# PROTOTYPE_G431_4IN1_v1_0.net
KiCad netlist of a schematic drawn in Altium Designer
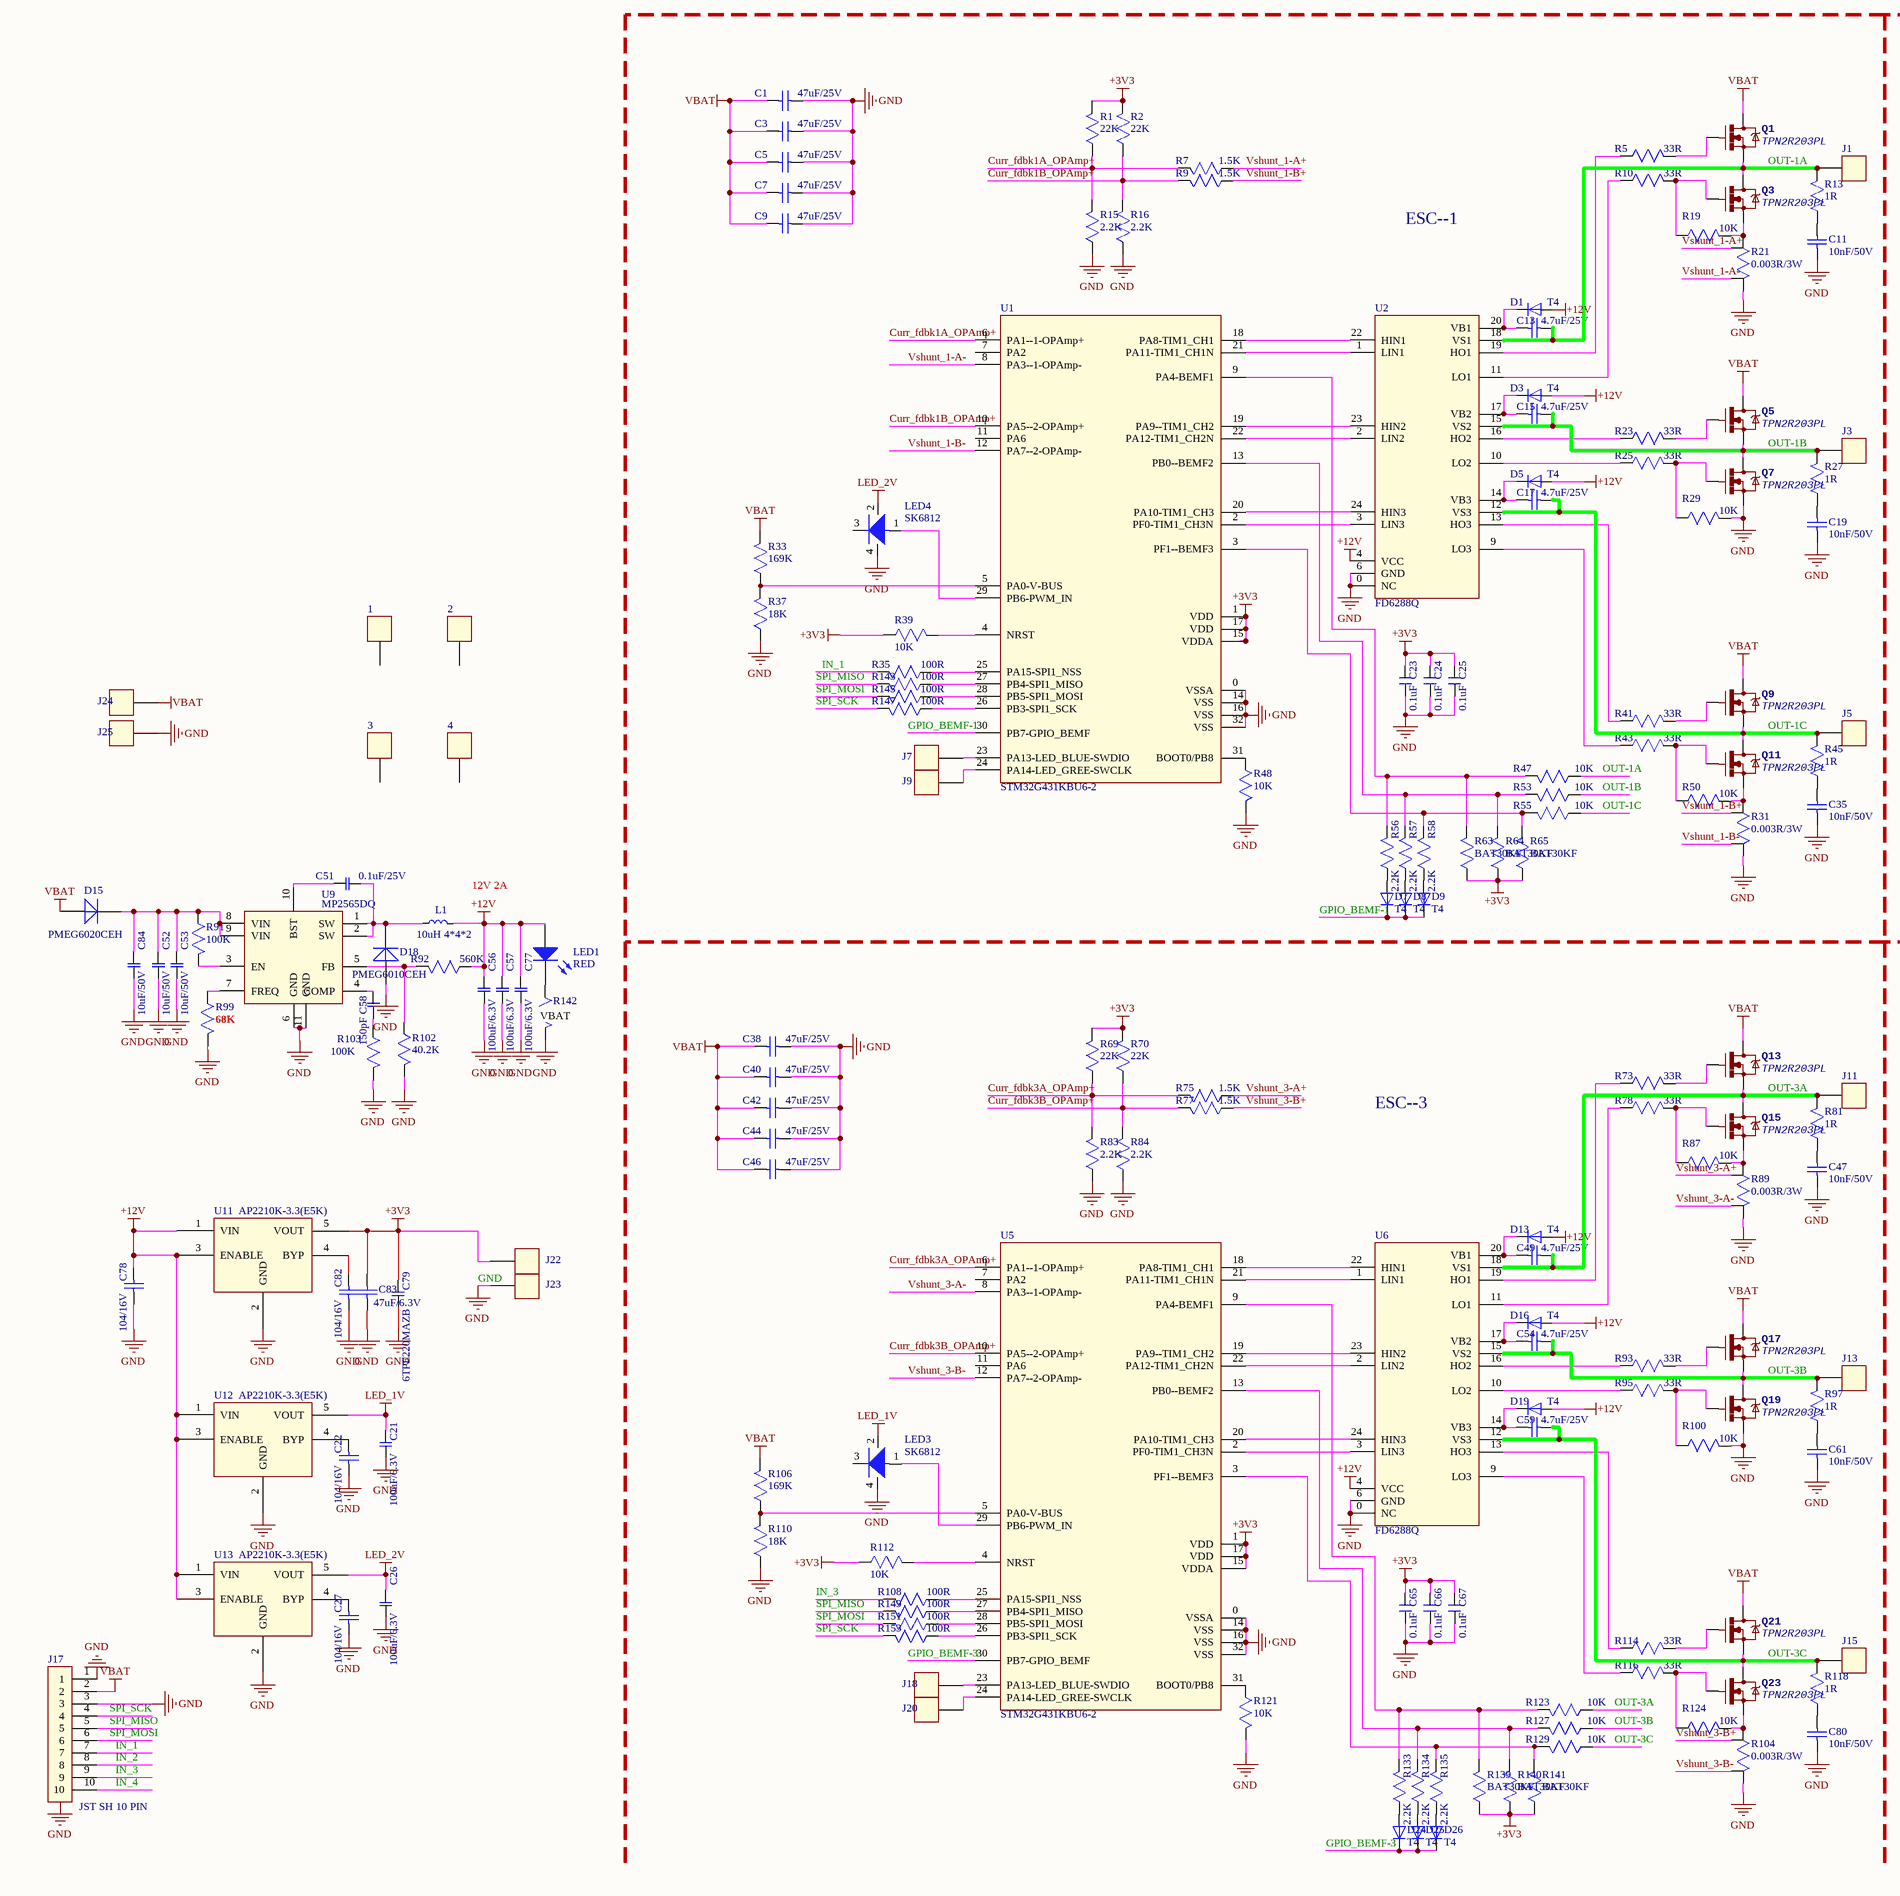
[diagram p0: PROTOTYPE_G431_4IN1_v1.0.SCHDOC, left]
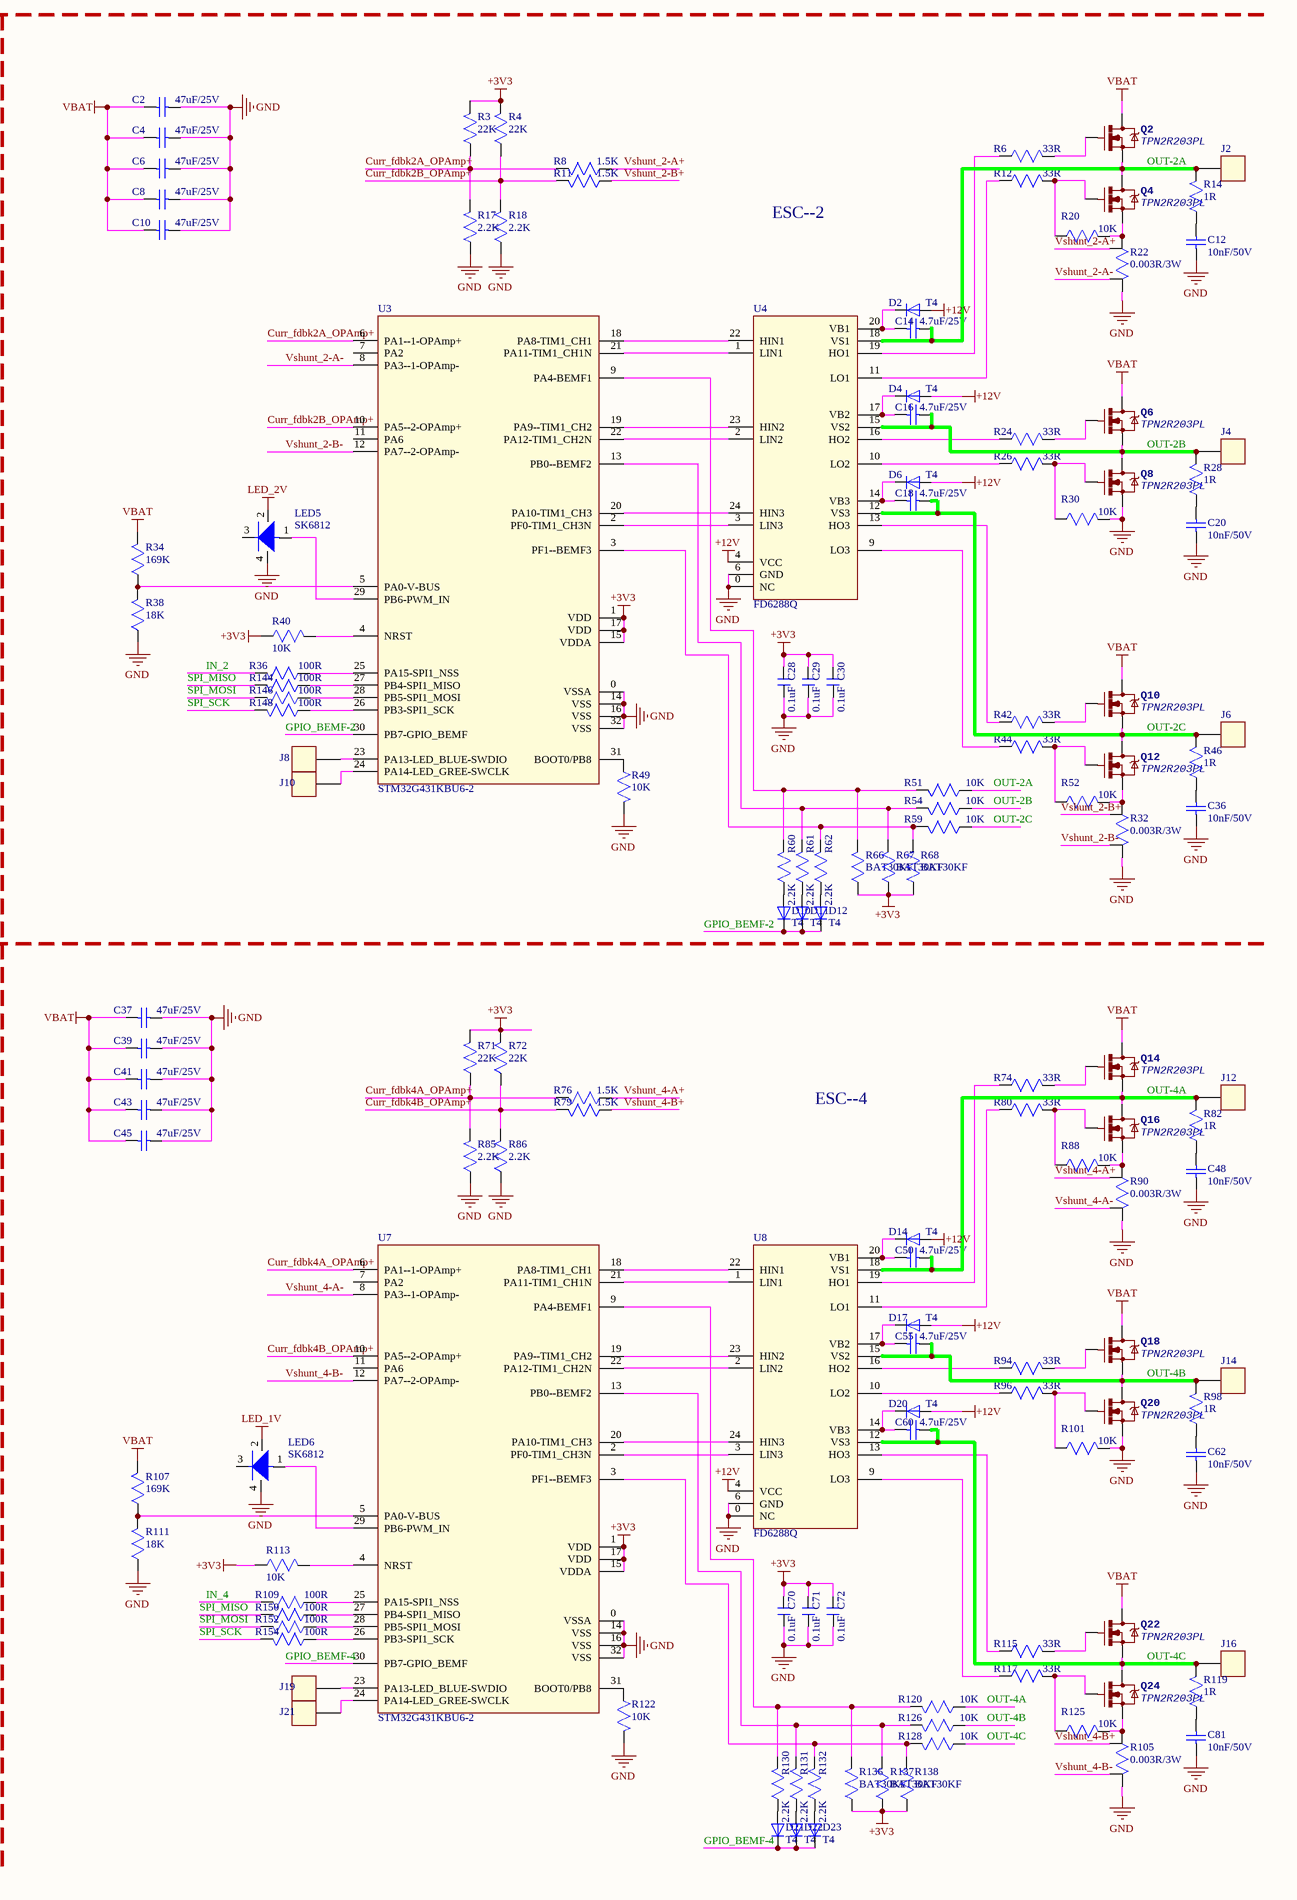
[diagram p1: PROTOTYPE_G431_4IN1_v1.0.SCHDOC, right]

(export (version "E")
  (design (tool "Eeschema 10.0.6"))
  (components
    (comp (ref "1") (value "~") (footprint "PAD-0.1") (libsource (lib "sf3") (part "PAD")))
    (comp (ref "2") (value "~") (footprint "PAD-0.1") (libsource (lib "sf3") (part "PAD")))
    (comp (ref "3") (value "~") (footprint "PAD-0.1") (libsource (lib "sf3") (part "PAD")))
    (comp (ref "4") (value "~") (footprint "PAD-0.1") (libsource (lib "sf3") (part "PAD")))
    (comp (ref "C1")
      (value "47uF/25V")
      (footprint "1206-RES")
      (description "Capacitor")
      (fields (field (name "PUBLISHER") "Altium Limited"))
      (libsource (lib "Miscellaneous Devices") (part "Cap"))
    )
    (comp (ref "C2")
      (value "47uF/25V")
      (footprint "1206-RES")
      (description "Capacitor")
      (fields (field (name "PUBLISHER") "Altium Limited"))
      (libsource (lib "Miscellaneous Devices") (part "Cap"))
    )
    (comp (ref "C3")
      (value "47uF/25V")
      (footprint "1206-RES")
      (description "Capacitor")
      (fields (field (name "PUBLISHER") "Altium Limited"))
      (libsource (lib "Miscellaneous Devices") (part "Cap"))
    )
    (comp (ref "C4")
      (value "47uF/25V")
      (footprint "1206-RES")
      (description "Capacitor")
      (fields (field (name "PUBLISHER") "Altium Limited"))
      (libsource (lib "Miscellaneous Devices") (part "Cap"))
    )
    (comp (ref "C5")
      (value "47uF/25V")
      (footprint "1206-RES")
      (description "Capacitor")
      (fields (field (name "PUBLISHER") "Altium Limited"))
      (libsource (lib "Miscellaneous Devices") (part "Cap"))
    )
    (comp (ref "C6")
      (value "47uF/25V")
      (footprint "1206-RES")
      (description "Capacitor")
      (fields (field (name "PUBLISHER") "Altium Limited"))
      (libsource (lib "Miscellaneous Devices") (part "Cap"))
    )
    (comp (ref "C7")
      (value "47uF/25V")
      (footprint "1206-RES")
      (description "Capacitor")
      (fields (field (name "PUBLISHER") "Altium Limited"))
      (libsource (lib "Miscellaneous Devices") (part "Cap"))
    )
    (comp (ref "C8")
      (value "47uF/25V")
      (footprint "1206-RES")
      (description "Capacitor")
      (fields (field (name "PUBLISHER") "Altium Limited"))
      (libsource (lib "Miscellaneous Devices") (part "Cap"))
    )
    (comp (ref "C9")
      (value "47uF/25V")
      (footprint "1206-RES")
      (description "Capacitor")
      (fields (field (name "PUBLISHER") "Altium Limited"))
      (libsource (lib "Miscellaneous Devices") (part "Cap"))
    )
    (comp (ref "C10")
      (value "47uF/25V")
      (footprint "1206-RES")
      (description "Capacitor")
      (fields (field (name "PUBLISHER") "Altium Limited"))
      (libsource (lib "Miscellaneous Devices") (part "Cap"))
    )
    (comp (ref "C11")
      (value "10nF/50V")
      (footprint "0402-RES")
      (fields (field (name "PUBLISHER") "Altium Limited"))
      (libsource (lib "DYS-XM30A V3.0") (part "Cap"))
    )
    (comp (ref "C12")
      (value "10nF/50V")
      (footprint "0402-RES")
      (fields (field (name "PUBLISHER") "Altium Limited"))
      (libsource (lib "DYS-XM30A V3.0") (part "Cap"))
    )
    (comp (ref "C13")
      (value "4.7uF/25V")
      (footprint "0603-RES")
      (fields (field (name "PUBLISHER") "Altium Limited"))
      (libsource (lib "DYS-XM30A V3.0") (part "Cap"))
    )
    (comp (ref "C14")
      (value "4.7uF/25V")
      (footprint "0603-RES")
      (fields (field (name "PUBLISHER") "Altium Limited"))
      (libsource (lib "DYS-XM30A V3.0") (part "Cap"))
    )
    (comp (ref "C15")
      (value "4.7uF/25V")
      (footprint "0603-RES")
      (fields (field (name "PUBLISHER") "Altium Limited"))
      (libsource (lib "DYS-XM30A V3.0") (part "Cap"))
    )
    (comp (ref "C16")
      (value "4.7uF/25V")
      (footprint "0603-RES")
      (fields (field (name "PUBLISHER") "Altium Limited"))
      (libsource (lib "DYS-XM30A V3.0") (part "Cap"))
    )
    (comp (ref "C17")
      (value "4.7uF/25V")
      (footprint "0603-RES")
      (fields (field (name "PUBLISHER") "Altium Limited"))
      (libsource (lib "DYS-XM30A V3.0") (part "Cap"))
    )
    (comp (ref "C18")
      (value "4.7uF/25V")
      (footprint "0603-RES")
      (fields (field (name "PUBLISHER") "Altium Limited"))
      (libsource (lib "DYS-XM30A V3.0") (part "Cap"))
    )
    (comp (ref "C19")
      (value "10nF/50V")
      (footprint "0402-RES")
      (fields (field (name "PUBLISHER") "Altium Limited"))
      (libsource (lib "DYS-XM30A V3.0") (part "Cap"))
    )
    (comp (ref "C20")
      (value "10nF/50V")
      (footprint "0402-RES")
      (fields (field (name "PUBLISHER") "Altium Limited"))
      (libsource (lib "DYS-XM30A V3.0") (part "Cap"))
    )
    (comp (ref "C21") (value "100uF/6.3V") (footprint "1206-RES") (libsource (lib "sf3") (part "C")))
    (comp (ref "C22")
      (value "104/16V")
      (footprint "0402-RES")
      (description "Capacitor")
      (fields (field (name "PUBLISHER") "Altium Limited"))
      (libsource (lib "Miscellaneous Devices") (part "Cap"))
    )
    (comp (ref "C23") (value "0.1uF") (footprint "0402-RES") (libsource (lib "USER-2016") (part "CAP")))
    (comp (ref "C24") (value "0.1uF") (footprint "0402-RES") (libsource (lib "USER-2016") (part "CAP")))
    (comp (ref "C25") (value "0.1uF") (footprint "0402-RES") (libsource (lib "USER-2016") (part "CAP")))
    (comp (ref "C26") (value "100uF/6.3V") (footprint "1206-RES") (libsource (lib "sf3") (part "C")))
    (comp (ref "C27")
      (value "104/16V")
      (footprint "0402-RES")
      (description "Capacitor")
      (fields (field (name "PUBLISHER") "Altium Limited"))
      (libsource (lib "Miscellaneous Devices") (part "Cap"))
    )
    (comp (ref "C28") (value "0.1uF") (footprint "0402-RES") (libsource (lib "USER-2016") (part "CAP")))
    (comp (ref "C29") (value "0.1uF") (footprint "0402-RES") (libsource (lib "USER-2016") (part "CAP")))
    (comp (ref "C30") (value "0.1uF") (footprint "0402-RES") (libsource (lib "USER-2016") (part "CAP")))
    (comp (ref "C35")
      (value "10nF/50V")
      (footprint "0402-RES")
      (fields (field (name "PUBLISHER") "Altium Limited"))
      (libsource (lib "DYS-XM30A V3.0") (part "Cap"))
    )
    (comp (ref "C36")
      (value "10nF/50V")
      (footprint "0402-RES")
      (fields (field (name "PUBLISHER") "Altium Limited"))
      (libsource (lib "DYS-XM30A V3.0") (part "Cap"))
    )
    (comp (ref "C37")
      (value "47uF/25V")
      (footprint "1206-RES")
      (description "Capacitor")
      (fields (field (name "PUBLISHER") "Altium Limited"))
      (libsource (lib "Miscellaneous Devices") (part "Cap"))
    )
    (comp (ref "C38")
      (value "47uF/25V")
      (footprint "1206-RES")
      (description "Capacitor")
      (fields (field (name "PUBLISHER") "Altium Limited"))
      (libsource (lib "Miscellaneous Devices") (part "Cap"))
    )
    (comp (ref "C39")
      (value "47uF/25V")
      (footprint "1206-RES")
      (description "Capacitor")
      (fields (field (name "PUBLISHER") "Altium Limited"))
      (libsource (lib "Miscellaneous Devices") (part "Cap"))
    )
    (comp (ref "C40")
      (value "47uF/25V")
      (footprint "1206-RES")
      (description "Capacitor")
      (fields (field (name "PUBLISHER") "Altium Limited"))
      (libsource (lib "Miscellaneous Devices") (part "Cap"))
    )
    (comp (ref "C41")
      (value "47uF/25V")
      (footprint "1206-RES")
      (description "Capacitor")
      (fields (field (name "PUBLISHER") "Altium Limited"))
      (libsource (lib "Miscellaneous Devices") (part "Cap"))
    )
    (comp (ref "C42")
      (value "47uF/25V")
      (footprint "1206-RES")
      (description "Capacitor")
      (fields (field (name "PUBLISHER") "Altium Limited"))
      (libsource (lib "Miscellaneous Devices") (part "Cap"))
    )
    (comp (ref "C43")
      (value "47uF/25V")
      (footprint "1206-RES")
      (description "Capacitor")
      (fields (field (name "PUBLISHER") "Altium Limited"))
      (libsource (lib "Miscellaneous Devices") (part "Cap"))
    )
    (comp (ref "C44")
      (value "47uF/25V")
      (footprint "1206-RES")
      (description "Capacitor")
      (fields (field (name "PUBLISHER") "Altium Limited"))
      (libsource (lib "Miscellaneous Devices") (part "Cap"))
    )
    (comp (ref "C45")
      (value "47uF/25V")
      (footprint "1206-RES")
      (description "Capacitor")
      (fields (field (name "PUBLISHER") "Altium Limited"))
      (libsource (lib "Miscellaneous Devices") (part "Cap"))
    )
    (comp (ref "C46")
      (value "47uF/25V")
      (footprint "1206-RES")
      (description "Capacitor")
      (fields (field (name "PUBLISHER") "Altium Limited"))
      (libsource (lib "Miscellaneous Devices") (part "Cap"))
    )
    (comp (ref "C47")
      (value "10nF/50V")
      (footprint "0402-RES")
      (fields (field (name "PUBLISHER") "Altium Limited"))
      (libsource (lib "DYS-XM30A V3.0") (part "Cap"))
    )
    (comp (ref "C48")
      (value "10nF/50V")
      (footprint "0402-RES")
      (fields (field (name "PUBLISHER") "Altium Limited"))
      (libsource (lib "DYS-XM30A V3.0") (part "Cap"))
    )
    (comp (ref "C49")
      (value "4.7uF/25V")
      (footprint "0603-RES")
      (fields (field (name "PUBLISHER") "Altium Limited"))
      (libsource (lib "DYS-XM30A V3.0") (part "Cap"))
    )
    (comp (ref "C50")
      (value "4.7uF/25V")
      (footprint "0603-RES")
      (fields (field (name "PUBLISHER") "Altium Limited"))
      (libsource (lib "DYS-XM30A V3.0") (part "Cap"))
    )
    (comp (ref "C51") (value "0.1uF/25V") (footprint "0402-RES") (libsource (lib "sf3") (part "C")))
    (comp (ref "C52") (value "10uF/50V") (footprint "1206-RES") (libsource (lib "sf3") (part "C")))
    (comp (ref "C53") (value "10uF/50V") (footprint "1206-RES") (libsource (lib "sf3") (part "C")))
    (comp (ref "C54")
      (value "4.7uF/25V")
      (footprint "0603-RES")
      (fields (field (name "PUBLISHER") "Altium Limited"))
      (libsource (lib "DYS-XM30A V3.0") (part "Cap"))
    )
    (comp (ref "C55")
      (value "4.7uF/25V")
      (footprint "0603-RES")
      (fields (field (name "PUBLISHER") "Altium Limited"))
      (libsource (lib "DYS-XM30A V3.0") (part "Cap"))
    )
    (comp (ref "C56") (value "100uF/6.3V") (footprint "1206-RES") (libsource (lib "sf3") (part "C")))
    (comp (ref "C57") (value "100uF/6.3V") (footprint "1206-RES") (libsource (lib "sf3") (part "C")))
    (comp (ref "C58") (value "150pF") (footprint "0402-RES") (libsource (lib "sf3") (part "C")))
    (comp (ref "C59")
      (value "4.7uF/25V")
      (footprint "0603-RES")
      (fields (field (name "PUBLISHER") "Altium Limited"))
      (libsource (lib "DYS-XM30A V3.0") (part "Cap"))
    )
    (comp (ref "C60")
      (value "4.7uF/25V")
      (footprint "0603-RES")
      (fields (field (name "PUBLISHER") "Altium Limited"))
      (libsource (lib "DYS-XM30A V3.0") (part "Cap"))
    )
    (comp (ref "C61")
      (value "10nF/50V")
      (footprint "0402-RES")
      (fields (field (name "PUBLISHER") "Altium Limited"))
      (libsource (lib "DYS-XM30A V3.0") (part "Cap"))
    )
    (comp (ref "C62")
      (value "10nF/50V")
      (footprint "0402-RES")
      (fields (field (name "PUBLISHER") "Altium Limited"))
      (libsource (lib "DYS-XM30A V3.0") (part "Cap"))
    )
    (comp (ref "C65") (value "0.1uF") (footprint "0402-RES") (libsource (lib "USER-2016") (part "CAP")))
    (comp (ref "C66") (value "0.1uF") (footprint "0402-RES") (libsource (lib "USER-2016") (part "CAP")))
    (comp (ref "C67") (value "0.1uF") (footprint "0402-RES") (libsource (lib "USER-2016") (part "CAP")))
    (comp (ref "C70") (value "0.1uF") (footprint "0402-RES") (libsource (lib "USER-2016") (part "CAP")))
    (comp (ref "C71") (value "0.1uF") (footprint "0402-RES") (libsource (lib "USER-2016") (part "CAP")))
    (comp (ref "C72") (value "0.1uF") (footprint "0402-RES") (libsource (lib "USER-2016") (part "CAP")))
    (comp (ref "C77") (value "100uF/6.3V") (footprint "1206-RES") (libsource (lib "sf3") (part "C")))
    (comp (ref "C78")
      (value "104/16V")
      (footprint "0402-RES")
      (description "Capacitor")
      (fields (field (name "PUBLISHER") "Altium Limited"))
      (libsource (lib "Miscellaneous Devices") (part "Cap"))
    )
    (comp (ref "C79") (value "6TPE220MAZB") (footprint "3528-CAP") (libsource (lib "USER-2016") (part "C")))
    (comp (ref "C80")
      (value "10nF/50V")
      (footprint "0402-RES")
      (fields (field (name "PUBLISHER") "Altium Limited"))
      (libsource (lib "DYS-XM30A V3.0") (part "Cap"))
    )
    (comp (ref "C81")
      (value "10nF/50V")
      (footprint "0402-RES")
      (fields (field (name "PUBLISHER") "Altium Limited"))
      (libsource (lib "DYS-XM30A V3.0") (part "Cap"))
    )
    (comp (ref "C82")
      (value "104/16V")
      (footprint "0402-RES")
      (description "Capacitor")
      (fields (field (name "PUBLISHER") "Altium Limited"))
      (libsource (lib "Miscellaneous Devices") (part "Cap"))
    )
    (comp (ref "C83")
      (value "47uF/6.3V")
      (footprint "0805-RES")
      (description "Capacitor")
      (fields (field (name "PUBLISHER") "Altium Limited"))
      (libsource (lib "Miscellaneous Devices") (part "Cap"))
    )
    (comp (ref "C84") (value "10uF/50V") (footprint "1206-RES") (libsource (lib "sf3") (part "C")))
    (comp (ref "D1") (value "T4") (footprint "SOD523") (libsource (lib "USER-2016") (part "DIODE")))
    (comp (ref "D2") (value "T4") (footprint "SOD523") (libsource (lib "USER-2016") (part "DIODE")))
    (comp (ref "D3") (value "T4") (footprint "SOD523") (libsource (lib "USER-2016") (part "DIODE")))
    (comp (ref "D4") (value "T4") (footprint "SOD523") (libsource (lib "USER-2016") (part "DIODE")))
    (comp (ref "D5") (value "T4") (footprint "SOD523") (libsource (lib "USER-2016") (part "DIODE")))
    (comp (ref "D6") (value "T4") (footprint "SOD523") (libsource (lib "USER-2016") (part "DIODE")))
    (comp (ref "D7") (value "T4") (footprint "SOD-723") (libsource (lib "USER-2016") (part "DIODE")))
    (comp (ref "D8") (value "T4") (footprint "SOD-723") (libsource (lib "USER-2016") (part "DIODE")))
    (comp (ref "D9") (value "T4") (footprint "SOD-723") (libsource (lib "USER-2016") (part "DIODE")))
    (comp (ref "D10") (value "T4") (footprint "SOD-723") (libsource (lib "USER-2016") (part "DIODE")))
    (comp (ref "D11") (value "T4") (footprint "SOD-723") (libsource (lib "USER-2016") (part "DIODE")))
    (comp (ref "D12") (value "T4") (footprint "SOD-723") (libsource (lib "USER-2016") (part "DIODE")))
    (comp (ref "D13") (value "T4") (footprint "SOD523") (libsource (lib "USER-2016") (part "DIODE")))
    (comp (ref "D14") (value "T4") (footprint "SOD523") (libsource (lib "USER-2016") (part "DIODE")))
    (comp (ref "D15") (value "PMEG6020CEH") (footprint "SOD123W") (libsource (lib "") (part "DIODE_1")))
    (comp (ref "D16") (value "T4") (footprint "SOD523") (libsource (lib "USER-2016") (part "DIODE")))
    (comp (ref "D17") (value "T4") (footprint "SOD523") (libsource (lib "USER-2016") (part "DIODE")))
    (comp (ref "D18") (value "PMEG6010CEH") (footprint "SOD123W") (libsource (lib "") (part "DIODE_1")))
    (comp (ref "D19") (value "T4") (footprint "SOD523") (libsource (lib "USER-2016") (part "DIODE")))
    (comp (ref "D20") (value "T4") (footprint "SOD523") (libsource (lib "USER-2016") (part "DIODE")))
    (comp (ref "D21") (value "T4") (footprint "SOD-723") (libsource (lib "USER-2016") (part "DIODE")))
    (comp (ref "D22") (value "T4") (footprint "SOD-723") (libsource (lib "USER-2016") (part "DIODE")))
    (comp (ref "D23") (value "T4") (footprint "SOD-723") (libsource (lib "USER-2016") (part "DIODE")))
    (comp (ref "D24") (value "T4") (footprint "SOD-723") (libsource (lib "USER-2016") (part "DIODE")))
    (comp (ref "D25") (value "T4") (footprint "SOD-723") (libsource (lib "USER-2016") (part "DIODE")))
    (comp (ref "D26") (value "T4") (footprint "SOD-723") (libsource (lib "USER-2016") (part "DIODE")))
    (comp (ref "J1") (value "~") (footprint "PAD-1  4*3") (libsource (lib "USER-2016") (part "PAD")))
    (comp (ref "J2") (value "~") (footprint "PAD-1  4*3") (libsource (lib "USER-2016") (part "PAD")))
    (comp (ref "J3") (value "~") (footprint "PAD-1  4*3") (libsource (lib "USER-2016") (part "PAD")))
    (comp (ref "J4") (value "~") (footprint "PAD-1  4*3") (libsource (lib "USER-2016") (part "PAD")))
    (comp (ref "J5") (value "~") (footprint "PAD-1  4*3") (libsource (lib "USER-2016") (part "PAD")))
    (comp (ref "J6") (value "~") (footprint "PAD-1  4*3") (libsource (lib "USER-2016") (part "PAD")))
    (comp (ref "J7") (value "~") (footprint "PAD-1  1*1.5") (libsource (lib "") (part "PAD_1")))
    (comp (ref "J8") (value "~") (footprint "PAD-1  1*1.5") (libsource (lib "") (part "PAD_1")))
    (comp (ref "J9") (value "~") (footprint "PAD-1  1*1.5") (libsource (lib "") (part "PAD_1")))
    (comp (ref "J10") (value "~") (footprint "PAD-1  1*1.5") (libsource (lib "") (part "PAD_1")))
    (comp (ref "J11") (value "~") (footprint "PAD-1  4*3") (libsource (lib "USER-2016") (part "PAD")))
    (comp (ref "J12") (value "~") (footprint "PAD-1  4*3") (libsource (lib "USER-2016") (part "PAD")))
    (comp (ref "J13") (value "~") (footprint "PAD-1  4*3") (libsource (lib "USER-2016") (part "PAD")))
    (comp (ref "J14") (value "~") (footprint "PAD-1  4*3") (libsource (lib "USER-2016") (part "PAD")))
    (comp (ref "J15") (value "~") (footprint "PAD-1  4*3") (libsource (lib "USER-2016") (part "PAD")))
    (comp (ref "J16") (value "~") (footprint "PAD-1  4*3") (libsource (lib "USER-2016") (part "PAD")))
    (comp (ref "J17")
      (value "JST SH 10 PIN")
      (footprint "JST SH 10 PIN")
      (libsource (lib "USER-2016") (part "J_10P"))
    )
    (comp (ref "J18") (value "~") (footprint "PAD-1  1*1.5") (libsource (lib "") (part "PAD_1")))
    (comp (ref "J19") (value "~") (footprint "PAD-1  1*1.5") (libsource (lib "") (part "PAD_1")))
    (comp (ref "J20") (value "~") (footprint "PAD-1  1*1.5") (libsource (lib "") (part "PAD_1")))
    (comp (ref "J21") (value "~") (footprint "PAD-1  1*1.5") (libsource (lib "") (part "PAD_1")))
    (comp (ref "J22") (value "~") (footprint "PAD-1  1*1.5") (libsource (lib "USER-2016") (part "PAD")))
    (comp (ref "J23") (value "~") (footprint "PAD-1  1*1.5") (libsource (lib "USER-2016") (part "PAD")))
    (comp (ref "J24") (value "~") (footprint "PAD-1  1*1.5") (libsource (lib "") (part "PAD_1")))
    (comp (ref "J25") (value "~") (footprint "PAD-1  1*1.5") (libsource (lib "") (part "PAD_1")))
    (comp (ref "L1") (value "10uH 4*4*2") (footprint "LPS4018") (libsource (lib "sf3") (part "L")))
    (comp (ref "LED1")
      (value "RED")
      (footprint "0402-LED")
      (fields (field (name "PUBLISHER") "Altium Limited"))
      (libsource (lib "sf3") (part "LED1"))
    )
    (comp (ref "LED3") (value "SK6812") (footprint "SK6812") (libsource (lib "USER-2016") (part "SK6812")))
    (comp (ref "LED4") (value "SK6812") (footprint "SK6812") (libsource (lib "USER-2016") (part "SK6812")))
    (comp (ref "LED5") (value "SK6812") (footprint "SK6812") (libsource (lib "USER-2016") (part "SK6812")))
    (comp (ref "LED6") (value "SK6812") (footprint "SK6812") (libsource (lib "USER-2016") (part "SK6812")))
    (comp (ref "Q1") (value "TPN2R203PL") (footprint "DFN8") (libsource (lib "Schlib1") (part "TPN2R304PL")))
    (comp (ref "Q2") (value "TPN2R203PL") (footprint "DFN8") (libsource (lib "Schlib1") (part "TPN2R304PL")))
    (comp (ref "Q3") (value "TPN2R203PL") (footprint "DFN8") (libsource (lib "Schlib1") (part "TPN2R304PL")))
    (comp (ref "Q4") (value "TPN2R203PL") (footprint "DFN8") (libsource (lib "Schlib1") (part "TPN2R304PL")))
    (comp (ref "Q5") (value "TPN2R203PL") (footprint "DFN8") (libsource (lib "Schlib1") (part "TPN2R304PL")))
    (comp (ref "Q6") (value "TPN2R203PL") (footprint "DFN8") (libsource (lib "Schlib1") (part "TPN2R304PL")))
    (comp (ref "Q7") (value "TPN2R203PL") (footprint "DFN8") (libsource (lib "Schlib1") (part "TPN2R304PL")))
    (comp (ref "Q8") (value "TPN2R203PL") (footprint "DFN8") (libsource (lib "Schlib1") (part "TPN2R304PL")))
    (comp (ref "Q9") (value "TPN2R203PL") (footprint "DFN8") (libsource (lib "Schlib1") (part "TPN2R304PL")))
    (comp (ref "Q10") (value "TPN2R203PL") (footprint "DFN8") (libsource (lib "Schlib1") (part "TPN2R304PL")))
    (comp (ref "Q11") (value "TPN2R203PL") (footprint "DFN8") (libsource (lib "Schlib1") (part "TPN2R304PL")))
    (comp (ref "Q12") (value "TPN2R203PL") (footprint "DFN8") (libsource (lib "Schlib1") (part "TPN2R304PL")))
    (comp (ref "Q13") (value "TPN2R203PL") (footprint "DFN8") (libsource (lib "Schlib1") (part "TPN2R304PL")))
    (comp (ref "Q14") (value "TPN2R203PL") (footprint "DFN8") (libsource (lib "Schlib1") (part "TPN2R304PL")))
    (comp (ref "Q15") (value "TPN2R203PL") (footprint "DFN8") (libsource (lib "Schlib1") (part "TPN2R304PL")))
    (comp (ref "Q16") (value "TPN2R203PL") (footprint "DFN8") (libsource (lib "Schlib1") (part "TPN2R304PL")))
    (comp (ref "Q17") (value "TPN2R203PL") (footprint "DFN8") (libsource (lib "Schlib1") (part "TPN2R304PL")))
    (comp (ref "Q18") (value "TPN2R203PL") (footprint "DFN8") (libsource (lib "Schlib1") (part "TPN2R304PL")))
    (comp (ref "Q19") (value "TPN2R203PL") (footprint "DFN8") (libsource (lib "Schlib1") (part "TPN2R304PL")))
    (comp (ref "Q20") (value "TPN2R203PL") (footprint "DFN8") (libsource (lib "Schlib1") (part "TPN2R304PL")))
    (comp (ref "Q21") (value "TPN2R203PL") (footprint "DFN8") (libsource (lib "Schlib1") (part "TPN2R304PL")))
    (comp (ref "Q22") (value "TPN2R203PL") (footprint "DFN8") (libsource (lib "Schlib1") (part "TPN2R304PL")))
    (comp (ref "Q23") (value "TPN2R203PL") (footprint "DFN8") (libsource (lib "Schlib1") (part "TPN2R304PL")))
    (comp (ref "Q24") (value "TPN2R203PL") (footprint "DFN8") (libsource (lib "Schlib1") (part "TPN2R304PL")))
    (comp (ref "R1") (value "22K") (footprint "0402-RES") (libsource (lib "sf3") (part "R")))
    (comp (ref "R2") (value "22K") (footprint "0402-RES") (libsource (lib "sf3") (part "R")))
    (comp (ref "R3") (value "22K") (footprint "0402-RES") (libsource (lib "sf3") (part "R")))
    (comp (ref "R4") (value "22K") (footprint "0402-RES") (libsource (lib "sf3") (part "R")))
    (comp (ref "R5") (value "33R") (footprint "0402-RES") (libsource (lib "USER-2016") (part "R")))
    (comp (ref "R6") (value "33R") (footprint "0402-RES") (libsource (lib "USER-2016") (part "R")))
    (comp (ref "R7") (value "1.5K") (footprint "0402-RES") (libsource (lib "sf3") (part "R")))
    (comp (ref "R8") (value "1.5K") (footprint "0402-RES") (libsource (lib "sf3") (part "R")))
    (comp (ref "R9") (value "1.5K") (footprint "0402-RES") (libsource (lib "sf3") (part "R")))
    (comp (ref "R10") (value "33R") (footprint "0402-RES") (libsource (lib "USER-2016") (part "R")))
    (comp (ref "R11") (value "1.5K") (footprint "0402-RES") (libsource (lib "sf3") (part "R")))
    (comp (ref "R12") (value "33R") (footprint "0402-RES") (libsource (lib "USER-2016") (part "R")))
    (comp (ref "R13") (value "1R") (footprint "0402-RES") (libsource (lib "USER-2016") (part "R")))
    (comp (ref "R14") (value "1R") (footprint "0402-RES") (libsource (lib "USER-2016") (part "R")))
    (comp (ref "R15") (value "2.2K") (footprint "0402-RES") (libsource (lib "sf3") (part "R")))
    (comp (ref "R16") (value "2.2K") (footprint "0402-RES") (libsource (lib "sf3") (part "R")))
    (comp (ref "R17") (value "2.2K") (footprint "0402-RES") (libsource (lib "sf3") (part "R")))
    (comp (ref "R18") (value "2.2K") (footprint "0402-RES") (libsource (lib "sf3") (part "R")))
    (comp (ref "R19") (value "10K") (footprint "0402-RES") (libsource (lib "USER-2016") (part "R")))
    (comp (ref "R20") (value "10K") (footprint "0402-RES") (libsource (lib "USER-2016") (part "R")))
    (comp (ref "R21")
      (value "0.003R/3W")
      (footprint "2010-RES")
      (libsource (lib "USER-2016") (part "RES_4W"))
    )
    (comp (ref "R22")
      (value "0.003R/3W")
      (footprint "2010-RES")
      (libsource (lib "USER-2016") (part "RES_4W"))
    )
    (comp (ref "R23") (value "33R") (footprint "0402-RES") (libsource (lib "USER-2016") (part "R")))
    (comp (ref "R24") (value "33R") (footprint "0402-RES") (libsource (lib "USER-2016") (part "R")))
    (comp (ref "R25") (value "33R") (footprint "0402-RES") (libsource (lib "USER-2016") (part "R")))
    (comp (ref "R26") (value "33R") (footprint "0402-RES") (libsource (lib "USER-2016") (part "R")))
    (comp (ref "R27") (value "1R") (footprint "0402-RES") (libsource (lib "USER-2016") (part "R")))
    (comp (ref "R28") (value "1R") (footprint "0402-RES") (libsource (lib "USER-2016") (part "R")))
    (comp (ref "R29") (value "10K") (footprint "0402-RES") (libsource (lib "USER-2016") (part "R")))
    (comp (ref "R30") (value "10K") (footprint "0402-RES") (libsource (lib "USER-2016") (part "R")))
    (comp (ref "R31")
      (value "0.003R/3W")
      (footprint "2010-RES")
      (libsource (lib "USER-2016") (part "RES_4W"))
    )
    (comp (ref "R32")
      (value "0.003R/3W")
      (footprint "2010-RES")
      (libsource (lib "USER-2016") (part "RES_4W"))
    )
    (comp (ref "R33") (value "169K") (footprint "0402-RES") (libsource (lib "sf3") (part "R")))
    (comp (ref "R34") (value "169K") (footprint "0402-RES") (libsource (lib "sf3") (part "R")))
    (comp (ref "R35") (value "100R") (footprint "0402-RES") (libsource (lib "sf3") (part "R")))
    (comp (ref "R36") (value "100R") (footprint "0402-RES") (libsource (lib "sf3") (part "R")))
    (comp (ref "R37") (value "18K") (footprint "0402-RES") (libsource (lib "sf3") (part "R")))
    (comp (ref "R38") (value "18K") (footprint "0402-RES") (libsource (lib "sf3") (part "R")))
    (comp (ref "R39") (value "10K") (footprint "0402-RES") (libsource (lib "sf3") (part "R")))
    (comp (ref "R40") (value "10K") (footprint "0402-RES") (libsource (lib "sf3") (part "R")))
    (comp (ref "R41") (value "33R") (footprint "0402-RES") (libsource (lib "USER-2016") (part "R")))
    (comp (ref "R42") (value "33R") (footprint "0402-RES") (libsource (lib "USER-2016") (part "R")))
    (comp (ref "R43") (value "33R") (footprint "0402-RES") (libsource (lib "USER-2016") (part "R")))
    (comp (ref "R44") (value "33R") (footprint "0402-RES") (libsource (lib "USER-2016") (part "R")))
    (comp (ref "R45") (value "1R") (footprint "0402-RES") (libsource (lib "USER-2016") (part "R")))
    (comp (ref "R46") (value "1R") (footprint "0402-RES") (libsource (lib "USER-2016") (part "R")))
    (comp (ref "R47") (value "10K") (footprint "0402-RES") (libsource (lib "sf3") (part "R")))
    (comp (ref "R48") (value "10K") (footprint "0402-RES") (libsource (lib "sf3") (part "R")))
    (comp (ref "R49") (value "10K") (footprint "0402-RES") (libsource (lib "sf3") (part "R")))
    (comp (ref "R50") (value "10K") (footprint "0402-RES") (libsource (lib "USER-2016") (part "R")))
    (comp (ref "R51") (value "10K") (footprint "0402-RES") (libsource (lib "sf3") (part "R")))
    (comp (ref "R52") (value "10K") (footprint "0402-RES") (libsource (lib "USER-2016") (part "R")))
    (comp (ref "R53") (value "10K") (footprint "0402-RES") (libsource (lib "sf3") (part "R")))
    (comp (ref "R54") (value "10K") (footprint "0402-RES") (libsource (lib "sf3") (part "R")))
    (comp (ref "R55") (value "10K") (footprint "0402-RES") (libsource (lib "sf3") (part "R")))
    (comp (ref "R56") (value "2.2K") (footprint "0402-RES") (libsource (lib "sf3") (part "R")))
    (comp (ref "R57") (value "2.2K") (footprint "0402-RES") (libsource (lib "sf3") (part "R")))
    (comp (ref "R58") (value "2.2K") (footprint "0402-RES") (libsource (lib "sf3") (part "R")))
    (comp (ref "R59") (value "10K") (footprint "0402-RES") (libsource (lib "sf3") (part "R")))
    (comp (ref "R60") (value "2.2K") (footprint "0402-RES") (libsource (lib "sf3") (part "R")))
    (comp (ref "R61") (value "2.2K") (footprint "0402-RES") (libsource (lib "sf3") (part "R")))
    (comp (ref "R62") (value "2.2K") (footprint "0402-RES") (libsource (lib "sf3") (part "R")))
    (comp (ref "R63") (value "BAT30KF") (footprint "0402-RES") (libsource (lib "sf3") (part "R")))
    (comp (ref "R64") (value "BAT30KF") (footprint "0402-RES") (libsource (lib "sf3") (part "R")))
    (comp (ref "R65") (value "BAT30KF") (footprint "0402-RES") (libsource (lib "sf3") (part "R")))
    (comp (ref "R66") (value "BAT30KF") (footprint "0402-RES") (libsource (lib "sf3") (part "R")))
    (comp (ref "R67") (value "BAT30KF") (footprint "0402-RES") (libsource (lib "sf3") (part "R")))
    (comp (ref "R68") (value "BAT30KF") (footprint "0402-RES") (libsource (lib "sf3") (part "R")))
    (comp (ref "R69") (value "22K") (footprint "0402-RES") (libsource (lib "sf3") (part "R")))
    (comp (ref "R70") (value "22K") (footprint "0402-RES") (libsource (lib "sf3") (part "R")))
    (comp (ref "R71") (value "22K") (footprint "0402-RES") (libsource (lib "sf3") (part "R")))
    (comp (ref "R72") (value "22K") (footprint "0402-RES") (libsource (lib "sf3") (part "R")))
    (comp (ref "R73") (value "33R") (footprint "0402-RES") (libsource (lib "USER-2016") (part "R")))
    (comp (ref "R74") (value "33R") (footprint "0402-RES") (libsource (lib "USER-2016") (part "R")))
    (comp (ref "R75") (value "1.5K") (footprint "0402-RES") (libsource (lib "sf3") (part "R")))
    (comp (ref "R76") (value "1.5K") (footprint "0402-RES") (libsource (lib "sf3") (part "R")))
    (comp (ref "R77") (value "1.5K") (footprint "0402-RES") (libsource (lib "sf3") (part "R")))
    (comp (ref "R78") (value "33R") (footprint "0402-RES") (libsource (lib "USER-2016") (part "R")))
    (comp (ref "R79") (value "1.5K") (footprint "0402-RES") (libsource (lib "sf3") (part "R")))
    (comp (ref "R80") (value "33R") (footprint "0402-RES") (libsource (lib "USER-2016") (part "R")))
    (comp (ref "R81") (value "1R") (footprint "0402-RES") (libsource (lib "USER-2016") (part "R")))
    (comp (ref "R82") (value "1R") (footprint "0402-RES") (libsource (lib "USER-2016") (part "R")))
    (comp (ref "R83") (value "2.2K") (footprint "0402-RES") (libsource (lib "sf3") (part "R")))
    (comp (ref "R84") (value "2.2K") (footprint "0402-RES") (libsource (lib "sf3") (part "R")))
    (comp (ref "R85") (value "2.2K") (footprint "0402-RES") (libsource (lib "sf3") (part "R")))
    (comp (ref "R86") (value "2.2K") (footprint "0402-RES") (libsource (lib "sf3") (part "R")))
    (comp (ref "R87") (value "10K") (footprint "0402-RES") (libsource (lib "USER-2016") (part "R")))
    (comp (ref "R88") (value "10K") (footprint "0402-RES") (libsource (lib "USER-2016") (part "R")))
    (comp (ref "R89")
      (value "0.003R/3W")
      (footprint "2010-RES")
      (libsource (lib "USER-2016") (part "RES_4W"))
    )
    (comp (ref "R90")
      (value "0.003R/3W")
      (footprint "2010-RES")
      (libsource (lib "USER-2016") (part "RES_4W"))
    )
    (comp (ref "R91") (value "100K") (footprint "0402-RES") (libsource (lib "sf3") (part "R")))
    (comp (ref "R92") (value "560K") (footprint "0402-RES") (libsource (lib "sf3") (part "R")))
    (comp (ref "R93") (value "33R") (footprint "0402-RES") (libsource (lib "USER-2016") (part "R")))
    (comp (ref "R94") (value "33R") (footprint "0402-RES") (libsource (lib "USER-2016") (part "R")))
    (comp (ref "R95") (value "33R") (footprint "0402-RES") (libsource (lib "USER-2016") (part "R")))
    (comp (ref "R96") (value "33R") (footprint "0402-RES") (libsource (lib "USER-2016") (part "R")))
    (comp (ref "R97") (value "1R") (footprint "0402-RES") (libsource (lib "USER-2016") (part "R")))
    (comp (ref "R98") (value "1R") (footprint "0402-RES") (libsource (lib "USER-2016") (part "R")))
    (comp (ref "R99") (value "68K") (footprint "0402-RES") (libsource (lib "sf3") (part "R")))
    (comp (ref "R100") (value "10K") (footprint "0402-RES") (libsource (lib "USER-2016") (part "R")))
    (comp (ref "R101") (value "10K") (footprint "0402-RES") (libsource (lib "USER-2016") (part "R")))
    (comp (ref "R102") (value "40.2K") (footprint "0402-RES") (libsource (lib "sf3") (part "R")))
    (comp (ref "R103") (value "100K") (footprint "0402-RES") (libsource (lib "sf3") (part "R")))
    (comp (ref "R104")
      (value "0.003R/3W")
      (footprint "2010-RES")
      (libsource (lib "USER-2016") (part "RES_4W"))
    )
    (comp (ref "R105")
      (value "0.003R/3W")
      (footprint "2010-RES")
      (libsource (lib "USER-2016") (part "RES_4W"))
    )
    (comp (ref "R106") (value "169K") (footprint "0402-RES") (libsource (lib "sf3") (part "R")))
    (comp (ref "R107") (value "169K") (footprint "0402-RES") (libsource (lib "sf3") (part "R")))
    (comp (ref "R108") (value "100R") (footprint "0402-RES") (libsource (lib "sf3") (part "R")))
    (comp (ref "R109") (value "100R") (footprint "0402-RES") (libsource (lib "sf3") (part "R")))
    (comp (ref "R110") (value "18K") (footprint "0402-RES") (libsource (lib "sf3") (part "R")))
    (comp (ref "R111") (value "18K") (footprint "0402-RES") (libsource (lib "sf3") (part "R")))
    (comp (ref "R112") (value "10K") (footprint "0402-RES") (libsource (lib "sf3") (part "R")))
    (comp (ref "R113") (value "10K") (footprint "0402-RES") (libsource (lib "sf3") (part "R")))
    (comp (ref "R114") (value "33R") (footprint "0402-RES") (libsource (lib "USER-2016") (part "R")))
    (comp (ref "R115") (value "33R") (footprint "0402-RES") (libsource (lib "USER-2016") (part "R")))
    (comp (ref "R116") (value "33R") (footprint "0402-RES") (libsource (lib "USER-2016") (part "R")))
    (comp (ref "R117") (value "33R") (footprint "0402-RES") (libsource (lib "USER-2016") (part "R")))
    (comp (ref "R118") (value "1R") (footprint "0402-RES") (libsource (lib "USER-2016") (part "R")))
    (comp (ref "R119") (value "1R") (footprint "0402-RES") (libsource (lib "USER-2016") (part "R")))
    (comp (ref "R120") (value "10K") (footprint "0402-RES") (libsource (lib "sf3") (part "R")))
    (comp (ref "R121") (value "10K") (footprint "0402-RES") (libsource (lib "sf3") (part "R")))
    (comp (ref "R122") (value "10K") (footprint "0402-RES") (libsource (lib "sf3") (part "R")))
    (comp (ref "R123") (value "10K") (footprint "0402-RES") (libsource (lib "sf3") (part "R")))
    (comp (ref "R124") (value "10K") (footprint "0402-RES") (libsource (lib "USER-2016") (part "R")))
    (comp (ref "R125") (value "10K") (footprint "0402-RES") (libsource (lib "USER-2016") (part "R")))
    (comp (ref "R126") (value "10K") (footprint "0402-RES") (libsource (lib "sf3") (part "R")))
    (comp (ref "R127") (value "10K") (footprint "0402-RES") (libsource (lib "sf3") (part "R")))
    (comp (ref "R128") (value "10K") (footprint "0402-RES") (libsource (lib "sf3") (part "R")))
    (comp (ref "R129") (value "10K") (footprint "0402-RES") (libsource (lib "sf3") (part "R")))
    (comp (ref "R130") (value "2.2K") (footprint "0402-RES") (libsource (lib "sf3") (part "R")))
    (comp (ref "R131") (value "2.2K") (footprint "0402-RES") (libsource (lib "sf3") (part "R")))
    (comp (ref "R132") (value "2.2K") (footprint "0402-RES") (libsource (lib "sf3") (part "R")))
    (comp (ref "R133") (value "2.2K") (footprint "0402-RES") (libsource (lib "sf3") (part "R")))
    (comp (ref "R134") (value "2.2K") (footprint "0402-RES") (libsource (lib "sf3") (part "R")))
    (comp (ref "R135") (value "2.2K") (footprint "0402-RES") (libsource (lib "sf3") (part "R")))
    (comp (ref "R136") (value "BAT30KF") (footprint "0402-RES") (libsource (lib "sf3") (part "R")))
    (comp (ref "R137") (value "BAT30KF") (footprint "0402-RES") (libsource (lib "sf3") (part "R")))
    (comp (ref "R138") (value "BAT30KF") (footprint "0402-RES") (libsource (lib "sf3") (part "R")))
    (comp (ref "R139") (value "BAT30KF") (footprint "0402-RES") (libsource (lib "sf3") (part "R")))
    (comp (ref "R140") (value "BAT30KF") (footprint "0402-RES") (libsource (lib "sf3") (part "R")))
    (comp (ref "R141") (value "BAT30KF") (footprint "0402-RES") (libsource (lib "sf3") (part "R")))
    (comp (ref "R142") (value "1K") (footprint "0402-RES") (libsource (lib "sf3") (part "R")))
    (comp (ref "R143") (value "100R") (footprint "0402-RES") (libsource (lib "sf3") (part "R")))
    (comp (ref "R144") (value "100R") (footprint "0402-RES") (libsource (lib "sf3") (part "R")))
    (comp (ref "R145") (value "100R") (footprint "0402-RES") (libsource (lib "sf3") (part "R")))
    (comp (ref "R146") (value "100R") (footprint "0402-RES") (libsource (lib "sf3") (part "R")))
    (comp (ref "R147") (value "100R") (footprint "0402-RES") (libsource (lib "sf3") (part "R")))
    (comp (ref "R148") (value "100R") (footprint "0402-RES") (libsource (lib "sf3") (part "R")))
    (comp (ref "R149") (value "100R") (footprint "0402-RES") (libsource (lib "sf3") (part "R")))
    (comp (ref "R150") (value "100R") (footprint "0402-RES") (libsource (lib "sf3") (part "R")))
    (comp (ref "R151") (value "100R") (footprint "0402-RES") (libsource (lib "sf3") (part "R")))
    (comp (ref "R152") (value "100R") (footprint "0402-RES") (libsource (lib "sf3") (part "R")))
    (comp (ref "R153") (value "100R") (footprint "0402-RES") (libsource (lib "sf3") (part "R")))
    (comp (ref "R154") (value "100R") (footprint "0402-RES") (libsource (lib "sf3") (part "R")))
    (comp (ref "U1")
      (value "STM32G431KBU6-2")
      (footprint "UFQFPN32")
      (libsource (lib "USER-2016") (part "STM32G431KBU6-2"))
    )
    (comp (ref "U2") (value "FD6288Q") (footprint "QFN24") (libsource (lib "USER-2016") (part "FD6288Q-2")))
    (comp (ref "U3")
      (value "STM32G431KBU6-2")
      (footprint "UFQFPN32")
      (libsource (lib "USER-2016") (part "STM32G431KBU6-2"))
    )
    (comp (ref "U4") (value "FD6288Q") (footprint "QFN24") (libsource (lib "USER-2016") (part "FD6288Q-2")))
    (comp (ref "U5")
      (value "STM32G431KBU6-2")
      (footprint "UFQFPN32")
      (libsource (lib "USER-2016") (part "STM32G431KBU6-2"))
    )
    (comp (ref "U6") (value "FD6288Q") (footprint "QFN24") (libsource (lib "USER-2016") (part "FD6288Q-2")))
    (comp (ref "U7")
      (value "STM32G431KBU6-2")
      (footprint "UFQFPN32")
      (libsource (lib "USER-2016") (part "STM32G431KBU6-2"))
    )
    (comp (ref "U8") (value "FD6288Q") (footprint "QFN24") (libsource (lib "USER-2016") (part "FD6288Q-2")))
    (comp (ref "U9")
      (value "MP2565DQ")
      (footprint "QFN10")
      (libsource (lib "USER-2016") (part "MP4460DQ/4462DQ"))
    )
    (comp (ref "U11")
      (value "AP2210K-3.3(E5K)")
      (footprint "SOT23-5")
      (libsource (lib "USER-2016") (part "MIC5207"))
    )
    (comp (ref "U12")
      (value "AP2210K-3.3(E5K)")
      (footprint "SOT23-5")
      (libsource (lib "USER-2016") (part "MIC5207"))
    )
    (comp (ref "U13")
      (value "AP2210K-3.3(E5K)")
      (footprint "SOT23-5")
      (libsource (lib "USER-2016") (part "MIC5207"))
    )
  )
  (nets
    (net (code "1") (name "+3V3") (class "Default")
      (node (ref "C23") (pin "2") (pinfunction "2_2") (pintype "passive"))
      (node (ref "C24") (pin "2") (pinfunction "2_2") (pintype "passive"))
      (node (ref "C25") (pin "2") (pinfunction "2_2") (pintype "passive"))
      (node (ref "C28") (pin "2") (pinfunction "2_2") (pintype "passive"))
      (node (ref "C29") (pin "2") (pinfunction "2_2") (pintype "passive"))
      (node (ref "C30") (pin "2") (pinfunction "2_2") (pintype "passive"))
      (node (ref "C65") (pin "2") (pinfunction "2_2") (pintype "passive"))
      (node (ref "C66") (pin "2") (pinfunction "2_2") (pintype "passive"))
      (node (ref "C67") (pin "2") (pinfunction "2_2") (pintype "passive"))
      (node (ref "C70") (pin "2") (pinfunction "2_2") (pintype "passive"))
      (node (ref "C71") (pin "2") (pinfunction "2_2") (pintype "passive"))
      (node (ref "C72") (pin "2") (pinfunction "2_2") (pintype "passive"))
      (node (ref "C79") (pin "1") (pinfunction "1_1") (pintype "passive"))
      (node (ref "C83") (pin "2") (pinfunction "2_2") (pintype "passive"))
      (node (ref "J22") (pin "1") (pinfunction "1_1") (pintype "passive"))
      (node (ref "R1") (pin "2") (pinfunction "2_2") (pintype "passive"))
      (node (ref "R112") (pin "1") (pinfunction "1_1") (pintype "passive"))
      (node (ref "R113") (pin "1") (pinfunction "1_1") (pintype "passive"))
      (node (ref "R136") (pin "1") (pinfunction "1_1") (pintype "passive"))
      (node (ref "R137") (pin "1") (pinfunction "1_1") (pintype "passive"))
      (node (ref "R138") (pin "1") (pinfunction "1_1") (pintype "passive"))
      (node (ref "R139") (pin "1") (pinfunction "1_1") (pintype "passive"))
      (node (ref "R140") (pin "1") (pinfunction "1_1") (pintype "passive"))
      (node (ref "R141") (pin "1") (pinfunction "1_1") (pintype "passive"))
      (node (ref "R2") (pin "2") (pinfunction "2_2") (pintype "passive"))
      (node (ref "R3") (pin "2") (pinfunction "2_2") (pintype "passive"))
      (node (ref "R39") (pin "1") (pinfunction "1_1") (pintype "passive"))
      (node (ref "R4") (pin "2") (pinfunction "2_2") (pintype "passive"))
      (node (ref "R40") (pin "1") (pinfunction "1_1") (pintype "passive"))
      (node (ref "R63") (pin "1") (pinfunction "1_1") (pintype "passive"))
      (node (ref "R64") (pin "1") (pinfunction "1_1") (pintype "passive"))
      (node (ref "R65") (pin "1") (pinfunction "1_1") (pintype "passive"))
      (node (ref "R66") (pin "1") (pinfunction "1_1") (pintype "passive"))
      (node (ref "R67") (pin "1") (pinfunction "1_1") (pintype "passive"))
      (node (ref "R68") (pin "1") (pinfunction "1_1") (pintype "passive"))
      (node (ref "R69") (pin "2") (pinfunction "2_2") (pintype "passive"))
      (node (ref "R70") (pin "2") (pinfunction "2_2") (pintype "passive"))
      (node (ref "R71") (pin "2") (pinfunction "2_2") (pintype "passive"))
      (node (ref "R72") (pin "2") (pinfunction "2_2") (pintype "passive"))
      (node (ref "U1") (pin "1") (pinfunction "VDD_1") (pintype "passive"))
      (node (ref "U1") (pin "15") (pinfunction "VDDA_15") (pintype "passive"))
      (node (ref "U1") (pin "17") (pinfunction "VDD_17") (pintype "passive"))
      (node (ref "U11") (pin "5") (pinfunction "VOUT_5") (pintype "passive"))
      (node (ref "U3") (pin "1") (pinfunction "VDD_1") (pintype "passive"))
      (node (ref "U3") (pin "15") (pinfunction "VDDA_15") (pintype "passive"))
      (node (ref "U3") (pin "17") (pinfunction "VDD_17") (pintype "passive"))
      (node (ref "U5") (pin "1") (pinfunction "VDD_1") (pintype "passive"))
      (node (ref "U5") (pin "15") (pinfunction "VDDA_15") (pintype "passive"))
      (node (ref "U5") (pin "17") (pinfunction "VDD_17") (pintype "passive"))
      (node (ref "U7") (pin "1") (pinfunction "VDD_1") (pintype "passive"))
      (node (ref "U7") (pin "15") (pinfunction "VDDA_15") (pintype "passive"))
      (node (ref "U7") (pin "17") (pinfunction "VDD_17") (pintype "passive"))
    )
    (net (code "2") (name "+12V") (class "Default")
      (node (ref "C56") (pin "1") (pinfunction "1_1") (pintype "passive"))
      (node (ref "C57") (pin "1") (pinfunction "1_1") (pintype "passive"))
      (node (ref "C77") (pin "1") (pinfunction "1_1") (pintype "passive"))
      (node (ref "C78") (pin "2") (pinfunction "2_2") (pintype "passive"))
      (node (ref "D1") (pin "2") (pinfunction "2_2") (pintype "passive"))
      (node (ref "D13") (pin "2") (pinfunction "2_2") (pintype "passive"))
      (node (ref "D14") (pin "2") (pinfunction "2_2") (pintype "passive"))
      (node (ref "D16") (pin "2") (pinfunction "2_2") (pintype "passive"))
      (node (ref "D17") (pin "2") (pinfunction "2_2") (pintype "passive"))
      (node (ref "D19") (pin "2") (pinfunction "2_2") (pintype "passive"))
      (node (ref "D2") (pin "2") (pinfunction "2_2") (pintype "passive"))
      (node (ref "D20") (pin "2") (pinfunction "2_2") (pintype "passive"))
      (node (ref "D3") (pin "2") (pinfunction "2_2") (pintype "passive"))
      (node (ref "D4") (pin "2") (pinfunction "2_2") (pintype "passive"))
      (node (ref "D5") (pin "2") (pinfunction "2_2") (pintype "passive"))
      (node (ref "D6") (pin "2") (pinfunction "2_2") (pintype "passive"))
      (node (ref "L1") (pin "1") (pinfunction "1_1") (pintype "passive"))
      (node (ref "LED1") (pin "1") (pinfunction "1_1") (pintype "passive"))
      (node (ref "R92") (pin "1") (pinfunction "1_1") (pintype "passive"))
      (node (ref "U11") (pin "1") (pinfunction "VIN_1") (pintype "passive"))
      (node (ref "U11") (pin "3") (pinfunction "ENABLE_3") (pintype "passive"))
      (node (ref "U12") (pin "1") (pinfunction "VIN_1") (pintype "passive"))
      (node (ref "U12") (pin "3") (pinfunction "ENABLE_3") (pintype "passive"))
      (node (ref "U13") (pin "1") (pinfunction "VIN_1") (pintype "passive"))
      (node (ref "U13") (pin "3") (pinfunction "ENABLE_3") (pintype "passive"))
      (node (ref "U2") (pin "4") (pinfunction "VCC_4") (pintype "passive"))
      (node (ref "U4") (pin "4") (pinfunction "VCC_4") (pintype "passive"))
      (node (ref "U6") (pin "4") (pinfunction "VCC_4") (pintype "passive"))
      (node (ref "U8") (pin "4") (pinfunction "VCC_4") (pintype "passive"))
    )
    (net (code "3") (name "/Curr_fdbk1A_OPAmp+") (class "Default")
      (node (ref "R1") (pin "1") (pinfunction "1_1") (pintype "passive"))
      (node (ref "R15") (pin "2") (pinfunction "2_2") (pintype "passive"))
      (node (ref "R7") (pin "2") (pinfunction "2_2") (pintype "passive"))
      (node (ref "U1") (pin "6") (pinfunction "PA1--1-OPAmp+_6") (pintype "passive"))
    )
    (net (code "4") (name "/Curr_fdbk1B_OPAmp+") (class "Default")
      (node (ref "R16") (pin "2") (pinfunction "2_2") (pintype "passive"))
      (node (ref "R2") (pin "1") (pinfunction "1_1") (pintype "passive"))
      (node (ref "R9") (pin "2") (pinfunction "2_2") (pintype "passive"))
      (node (ref "U1") (pin "10") (pinfunction "PA5--2-OPAmp+_10") (pintype "passive"))
    )
    (net (code "5") (name "/Curr_fdbk2A_OPAmp+") (class "Default")
      (node (ref "R17") (pin "2") (pinfunction "2_2") (pintype "passive"))
      (node (ref "R3") (pin "1") (pinfunction "1_1") (pintype "passive"))
      (node (ref "R8") (pin "2") (pinfunction "2_2") (pintype "passive"))
      (node (ref "U3") (pin "6") (pinfunction "PA1--1-OPAmp+_6") (pintype "passive"))
    )
    (net (code "6") (name "/Curr_fdbk2B_OPAmp+") (class "Default")
      (node (ref "R11") (pin "2") (pinfunction "2_2") (pintype "passive"))
      (node (ref "R18") (pin "2") (pinfunction "2_2") (pintype "passive"))
      (node (ref "R4") (pin "1") (pinfunction "1_1") (pintype "passive"))
      (node (ref "U3") (pin "10") (pinfunction "PA5--2-OPAmp+_10") (pintype "passive"))
    )
    (net (code "7") (name "/Curr_fdbk3A_OPAmp+") (class "Default")
      (node (ref "R69") (pin "1") (pinfunction "1_1") (pintype "passive"))
      (node (ref "R75") (pin "2") (pinfunction "2_2") (pintype "passive"))
      (node (ref "R83") (pin "2") (pinfunction "2_2") (pintype "passive"))
      (node (ref "U5") (pin "6") (pinfunction "PA1--1-OPAmp+_6") (pintype "passive"))
    )
    (net (code "8") (name "/Curr_fdbk3B_OPAmp+") (class "Default")
      (node (ref "R70") (pin "1") (pinfunction "1_1") (pintype "passive"))
      (node (ref "R77") (pin "2") (pinfunction "2_2") (pintype "passive"))
      (node (ref "R84") (pin "2") (pinfunction "2_2") (pintype "passive"))
      (node (ref "U5") (pin "10") (pinfunction "PA5--2-OPAmp+_10") (pintype "passive"))
    )
    (net (code "9") (name "/Curr_fdbk4A_OPAmp+") (class "Default")
      (node (ref "R71") (pin "1") (pinfunction "1_1") (pintype "passive"))
      (node (ref "R76") (pin "2") (pinfunction "2_2") (pintype "passive"))
      (node (ref "R85") (pin "2") (pinfunction "2_2") (pintype "passive"))
      (node (ref "U7") (pin "6") (pinfunction "PA1--1-OPAmp+_6") (pintype "passive"))
    )
    (net (code "10") (name "/Curr_fdbk4B_OPAmp+") (class "Default")
      (node (ref "R72") (pin "1") (pinfunction "1_1") (pintype "passive"))
      (node (ref "R79") (pin "2") (pinfunction "2_2") (pintype "passive"))
      (node (ref "R86") (pin "2") (pinfunction "2_2") (pintype "passive"))
      (node (ref "U7") (pin "10") (pinfunction "PA5--2-OPAmp+_10") (pintype "passive"))
    )
    (net (code "11") (name "/GPIO_BEMF-1") (class "Default")
      (node (ref "D7") (pin "1") (pinfunction "1_1") (pintype "passive"))
      (node (ref "D8") (pin "1") (pinfunction "1_1") (pintype "passive"))
      (node (ref "D9") (pin "1") (pinfunction "1_1") (pintype "passive"))
      (node (ref "U1") (pin "30") (pinfunction "PB7-GPIO_BEMF_30") (pintype "passive"))
    )
    (net (code "12") (name "/GPIO_BEMF-2") (class "Default")
      (node (ref "D10") (pin "1") (pinfunction "1_1") (pintype "passive"))
      (node (ref "D11") (pin "1") (pinfunction "1_1") (pintype "passive"))
      (node (ref "D12") (pin "1") (pinfunction "1_1") (pintype "passive"))
      (node (ref "U3") (pin "30") (pinfunction "PB7-GPIO_BEMF_30") (pintype "passive"))
    )
    (net (code "13") (name "/GPIO_BEMF-3") (class "Default")
      (node (ref "D24") (pin "1") (pinfunction "1_1") (pintype "passive"))
      (node (ref "D25") (pin "1") (pinfunction "1_1") (pintype "passive"))
      (node (ref "D26") (pin "1") (pinfunction "1_1") (pintype "passive"))
      (node (ref "U5") (pin "30") (pinfunction "PB7-GPIO_BEMF_30") (pintype "passive"))
    )
    (net (code "14") (name "/GPIO_BEMF-4") (class "Default")
      (node (ref "D21") (pin "1") (pinfunction "1_1") (pintype "passive"))
      (node (ref "D22") (pin "1") (pinfunction "1_1") (pintype "passive"))
      (node (ref "D23") (pin "1") (pinfunction "1_1") (pintype "passive"))
      (node (ref "U7") (pin "30") (pinfunction "PB7-GPIO_BEMF_30") (pintype "passive"))
    )
    (net (code "15") (name "/IN_1") (class "Default")
      (node (ref "J17") (pin "7") (pinfunction "7_7") (pintype "passive"))
      (node (ref "R35") (pin "2") (pinfunction "2_2") (pintype "passive"))
    )
    (net (code "16") (name "/IN_2") (class "Default")
      (node (ref "J17") (pin "8") (pinfunction "8_8") (pintype "passive"))
      (node (ref "R36") (pin "2") (pinfunction "2_2") (pintype "passive"))
    )
    (net (code "17") (name "/IN_3") (class "Default")
      (node (ref "J17") (pin "9") (pinfunction "9_9") (pintype "passive"))
      (node (ref "R108") (pin "2") (pinfunction "2_2") (pintype "passive"))
    )
    (net (code "18") (name "/IN_4") (class "Default")
      (node (ref "J17") (pin "10") (pinfunction "10_10") (pintype "passive"))
      (node (ref "R109") (pin "2") (pinfunction "2_2") (pintype "passive"))
    )
    (net (code "19") (name "/OUT-1A") (class "Default")
      (node (ref "C13") (pin "1") (pinfunction "1_1") (pintype "passive"))
      (node (ref "J1") (pin "1") (pinfunction "1_1") (pintype "passive"))
      (node (ref "Q1") (pin "3") (pinfunction "S_3") (pintype "passive"))
      (node (ref "Q3") (pin "5") (pinfunction "D_5") (pintype "passive"))
      (node (ref "R13") (pin "2") (pinfunction "2_2") (pintype "passive"))
      (node (ref "R47") (pin "1") (pinfunction "1_1") (pintype "passive"))
      (node (ref "U2") (pin "18") (pinfunction "VS1_18") (pintype "passive"))
    )
    (net (code "20") (name "/OUT-1B") (class "Default")
      (node (ref "C15") (pin "1") (pinfunction "1_1") (pintype "passive"))
      (node (ref "J3") (pin "1") (pinfunction "1_1") (pintype "passive"))
      (node (ref "Q5") (pin "3") (pinfunction "S_3") (pintype "passive"))
      (node (ref "Q7") (pin "5") (pinfunction "D_5") (pintype "passive"))
      (node (ref "R27") (pin "2") (pinfunction "2_2") (pintype "passive"))
      (node (ref "R53") (pin "1") (pinfunction "1_1") (pintype "passive"))
      (node (ref "U2") (pin "15") (pinfunction "VS2_15") (pintype "passive"))
    )
    (net (code "21") (name "/OUT-1C") (class "Default")
      (node (ref "C17") (pin "1") (pinfunction "1_1") (pintype "passive"))
      (node (ref "J5") (pin "1") (pinfunction "1_1") (pintype "passive"))
      (node (ref "Q11") (pin "5") (pinfunction "D_5") (pintype "passive"))
      (node (ref "Q9") (pin "3") (pinfunction "S_3") (pintype "passive"))
      (node (ref "R45") (pin "2") (pinfunction "2_2") (pintype "passive"))
      (node (ref "R55") (pin "1") (pinfunction "1_1") (pintype "passive"))
      (node (ref "U2") (pin "12") (pinfunction "VS3_12") (pintype "passive"))
    )
    (net (code "22") (name "/OUT-2A") (class "Default")
      (node (ref "C14") (pin "1") (pinfunction "1_1") (pintype "passive"))
      (node (ref "J2") (pin "1") (pinfunction "1_1") (pintype "passive"))
      (node (ref "Q2") (pin "3") (pinfunction "S_3") (pintype "passive"))
      (node (ref "Q4") (pin "5") (pinfunction "D_5") (pintype "passive"))
      (node (ref "R14") (pin "2") (pinfunction "2_2") (pintype "passive"))
      (node (ref "R51") (pin "1") (pinfunction "1_1") (pintype "passive"))
      (node (ref "U4") (pin "18") (pinfunction "VS1_18") (pintype "passive"))
    )
    (net (code "23") (name "/OUT-2B") (class "Default")
      (node (ref "C16") (pin "1") (pinfunction "1_1") (pintype "passive"))
      (node (ref "J4") (pin "1") (pinfunction "1_1") (pintype "passive"))
      (node (ref "Q6") (pin "3") (pinfunction "S_3") (pintype "passive"))
      (node (ref "Q8") (pin "5") (pinfunction "D_5") (pintype "passive"))
      (node (ref "R28") (pin "2") (pinfunction "2_2") (pintype "passive"))
      (node (ref "R54") (pin "1") (pinfunction "1_1") (pintype "passive"))
      (node (ref "U4") (pin "15") (pinfunction "VS2_15") (pintype "passive"))
    )
    (net (code "24") (name "/OUT-2C") (class "Default")
      (node (ref "C18") (pin "1") (pinfunction "1_1") (pintype "passive"))
      (node (ref "J6") (pin "1") (pinfunction "1_1") (pintype "passive"))
      (node (ref "Q10") (pin "3") (pinfunction "S_3") (pintype "passive"))
      (node (ref "Q12") (pin "5") (pinfunction "D_5") (pintype "passive"))
      (node (ref "R46") (pin "2") (pinfunction "2_2") (pintype "passive"))
      (node (ref "R59") (pin "1") (pinfunction "1_1") (pintype "passive"))
      (node (ref "U4") (pin "12") (pinfunction "VS3_12") (pintype "passive"))
    )
    (net (code "25") (name "/OUT-3A") (class "Default")
      (node (ref "C49") (pin "1") (pinfunction "1_1") (pintype "passive"))
      (node (ref "J11") (pin "1") (pinfunction "1_1") (pintype "passive"))
      (node (ref "Q13") (pin "3") (pinfunction "S_3") (pintype "passive"))
      (node (ref "Q15") (pin "5") (pinfunction "D_5") (pintype "passive"))
      (node (ref "R123") (pin "1") (pinfunction "1_1") (pintype "passive"))
      (node (ref "R81") (pin "2") (pinfunction "2_2") (pintype "passive"))
      (node (ref "U6") (pin "18") (pinfunction "VS1_18") (pintype "passive"))
    )
    (net (code "26") (name "/OUT-3B") (class "Default")
      (node (ref "C54") (pin "1") (pinfunction "1_1") (pintype "passive"))
      (node (ref "J13") (pin "1") (pinfunction "1_1") (pintype "passive"))
      (node (ref "Q17") (pin "3") (pinfunction "S_3") (pintype "passive"))
      (node (ref "Q19") (pin "5") (pinfunction "D_5") (pintype "passive"))
      (node (ref "R127") (pin "1") (pinfunction "1_1") (pintype "passive"))
      (node (ref "R97") (pin "2") (pinfunction "2_2") (pintype "passive"))
      (node (ref "U6") (pin "15") (pinfunction "VS2_15") (pintype "passive"))
    )
    (net (code "27") (name "/OUT-3C") (class "Default")
      (node (ref "C59") (pin "1") (pinfunction "1_1") (pintype "passive"))
      (node (ref "J15") (pin "1") (pinfunction "1_1") (pintype "passive"))
      (node (ref "Q21") (pin "3") (pinfunction "S_3") (pintype "passive"))
      (node (ref "Q23") (pin "5") (pinfunction "D_5") (pintype "passive"))
      (node (ref "R118") (pin "2") (pinfunction "2_2") (pintype "passive"))
      (node (ref "R129") (pin "1") (pinfunction "1_1") (pintype "passive"))
      (node (ref "U6") (pin "12") (pinfunction "VS3_12") (pintype "passive"))
    )
    (net (code "28") (name "/OUT-4A") (class "Default")
      (node (ref "C50") (pin "1") (pinfunction "1_1") (pintype "passive"))
      (node (ref "J12") (pin "1") (pinfunction "1_1") (pintype "passive"))
      (node (ref "Q14") (pin "3") (pinfunction "S_3") (pintype "passive"))
      (node (ref "Q16") (pin "5") (pinfunction "D_5") (pintype "passive"))
      (node (ref "R120") (pin "1") (pinfunction "1_1") (pintype "passive"))
      (node (ref "R82") (pin "2") (pinfunction "2_2") (pintype "passive"))
      (node (ref "U8") (pin "18") (pinfunction "VS1_18") (pintype "passive"))
    )
    (net (code "29") (name "/OUT-4B") (class "Default")
      (node (ref "C55") (pin "1") (pinfunction "1_1") (pintype "passive"))
      (node (ref "J14") (pin "1") (pinfunction "1_1") (pintype "passive"))
      (node (ref "Q18") (pin "3") (pinfunction "S_3") (pintype "passive"))
      (node (ref "Q20") (pin "5") (pinfunction "D_5") (pintype "passive"))
      (node (ref "R126") (pin "1") (pinfunction "1_1") (pintype "passive"))
      (node (ref "R98") (pin "2") (pinfunction "2_2") (pintype "passive"))
      (node (ref "U8") (pin "15") (pinfunction "VS2_15") (pintype "passive"))
    )
    (net (code "30") (name "/OUT-4C") (class "Default")
      (node (ref "C60") (pin "1") (pinfunction "1_1") (pintype "passive"))
      (node (ref "J16") (pin "1") (pinfunction "1_1") (pintype "passive"))
      (node (ref "Q22") (pin "3") (pinfunction "S_3") (pintype "passive"))
      (node (ref "Q24") (pin "5") (pinfunction "D_5") (pintype "passive"))
      (node (ref "R119") (pin "2") (pinfunction "2_2") (pintype "passive"))
      (node (ref "R128") (pin "1") (pinfunction "1_1") (pintype "passive"))
      (node (ref "U8") (pin "12") (pinfunction "VS3_12") (pintype "passive"))
    )
    (net (code "31") (name "/SPI_MISO") (class "Default")
      (node (ref "J17") (pin "5") (pinfunction "5_5") (pintype "passive"))
      (node (ref "R143") (pin "2") (pinfunction "2_2") (pintype "passive"))
      (node (ref "R144") (pin "2") (pinfunction "2_2") (pintype "passive"))
      (node (ref "R149") (pin "2") (pinfunction "2_2") (pintype "passive"))
      (node (ref "R150") (pin "2") (pinfunction "2_2") (pintype "passive"))
    )
    (net (code "32") (name "/SPI_MOSI") (class "Default")
      (node (ref "J17") (pin "6") (pinfunction "6_6") (pintype "passive"))
      (node (ref "R145") (pin "2") (pinfunction "2_2") (pintype "passive"))
      (node (ref "R146") (pin "2") (pinfunction "2_2") (pintype "passive"))
      (node (ref "R151") (pin "2") (pinfunction "2_2") (pintype "passive"))
      (node (ref "R152") (pin "2") (pinfunction "2_2") (pintype "passive"))
    )
    (net (code "33") (name "/SPI_SCK") (class "Default")
      (node (ref "J17") (pin "4") (pinfunction "4_4") (pintype "passive"))
      (node (ref "R147") (pin "2") (pinfunction "2_2") (pintype "passive"))
      (node (ref "R148") (pin "2") (pinfunction "2_2") (pintype "passive"))
      (node (ref "R153") (pin "2") (pinfunction "2_2") (pintype "passive"))
      (node (ref "R154") (pin "2") (pinfunction "2_2") (pintype "passive"))
    )
    (net (code "34") (name "/Vshunt_1-A+") (class "Default")
      (node (ref "R21") (pin "3") (pinfunction "3_3") (pintype "passive"))
      (node (ref "R7") (pin "1") (pinfunction "1_1") (pintype "passive"))
    )
    (net (code "35") (name "/Vshunt_1-A-") (class "Default")
      (node (ref "R21") (pin "4") (pinfunction "4_4") (pintype "passive"))
      (node (ref "U1") (pin "8") (pinfunction "PA3--1-OPAmp-_8") (pintype "passive"))
    )
    (net (code "36") (name "/Vshunt_1-B+") (class "Default")
      (node (ref "R31") (pin "3") (pinfunction "3_3") (pintype "passive"))
      (node (ref "R9") (pin "1") (pinfunction "1_1") (pintype "passive"))
    )
    (net (code "37") (name "/Vshunt_1-B-") (class "Default")
      (node (ref "R31") (pin "4") (pinfunction "4_4") (pintype "passive"))
      (node (ref "U1") (pin "12") (pinfunction "PA7--2-OPAmp-_12") (pintype "passive"))
    )
    (net (code "38") (name "/Vshunt_2-A+") (class "Default")
      (node (ref "R22") (pin "3") (pinfunction "3_3") (pintype "passive"))
      (node (ref "R8") (pin "1") (pinfunction "1_1") (pintype "passive"))
    )
    (net (code "39") (name "/Vshunt_2-A-") (class "Default")
      (node (ref "R22") (pin "4") (pinfunction "4_4") (pintype "passive"))
      (node (ref "U3") (pin "8") (pinfunction "PA3--1-OPAmp-_8") (pintype "passive"))
    )
    (net (code "40") (name "/Vshunt_2-B+") (class "Default")
      (node (ref "R11") (pin "1") (pinfunction "1_1") (pintype "passive"))
      (node (ref "R32") (pin "3") (pinfunction "3_3") (pintype "passive"))
    )
    (net (code "41") (name "/Vshunt_2-B-") (class "Default")
      (node (ref "R32") (pin "4") (pinfunction "4_4") (pintype "passive"))
      (node (ref "U3") (pin "12") (pinfunction "PA7--2-OPAmp-_12") (pintype "passive"))
    )
    (net (code "42") (name "/Vshunt_3-A+") (class "Default")
      (node (ref "R75") (pin "1") (pinfunction "1_1") (pintype "passive"))
      (node (ref "R89") (pin "3") (pinfunction "3_3") (pintype "passive"))
    )
    (net (code "43") (name "/Vshunt_3-A-") (class "Default")
      (node (ref "R89") (pin "4") (pinfunction "4_4") (pintype "passive"))
      (node (ref "U5") (pin "8") (pinfunction "PA3--1-OPAmp-_8") (pintype "passive"))
    )
    (net (code "44") (name "/Vshunt_3-B+") (class "Default")
      (node (ref "R104") (pin "3") (pinfunction "3_3") (pintype "passive"))
      (node (ref "R77") (pin "1") (pinfunction "1_1") (pintype "passive"))
    )
    (net (code "45") (name "/Vshunt_3-B-") (class "Default")
      (node (ref "R104") (pin "4") (pinfunction "4_4") (pintype "passive"))
      (node (ref "U5") (pin "12") (pinfunction "PA7--2-OPAmp-_12") (pintype "passive"))
    )
    (net (code "46") (name "/Vshunt_4-A+") (class "Default")
      (node (ref "R76") (pin "1") (pinfunction "1_1") (pintype "passive"))
      (node (ref "R90") (pin "3") (pinfunction "3_3") (pintype "passive"))
    )
    (net (code "47") (name "/Vshunt_4-A-") (class "Default")
      (node (ref "R90") (pin "4") (pinfunction "4_4") (pintype "passive"))
      (node (ref "U7") (pin "8") (pinfunction "PA3--1-OPAmp-_8") (pintype "passive"))
    )
    (net (code "48") (name "/Vshunt_4-B+") (class "Default")
      (node (ref "R105") (pin "3") (pinfunction "3_3") (pintype "passive"))
      (node (ref "R79") (pin "1") (pinfunction "1_1") (pintype "passive"))
    )
    (net (code "49") (name "/Vshunt_4-B-") (class "Default")
      (node (ref "R105") (pin "4") (pinfunction "4_4") (pintype "passive"))
      (node (ref "U7") (pin "12") (pinfunction "PA7--2-OPAmp-_12") (pintype "passive"))
    )
    (net (code "50") (name "GND") (class "Default")
      (node (ref "C1") (pin "2") (pinfunction "2_2") (pintype "passive"))
      (node (ref "C10") (pin "2") (pinfunction "2_2") (pintype "passive"))
      (node (ref "C11") (pin "2") (pinfunction "2_2") (pintype "passive"))
      (node (ref "C12") (pin "2") (pinfunction "2_2") (pintype "passive"))
      (node (ref "C19") (pin "2") (pinfunction "2_2") (pintype "passive"))
      (node (ref "C2") (pin "2") (pinfunction "2_2") (pintype "passive"))
      (node (ref "C20") (pin "2") (pinfunction "2_2") (pintype "passive"))
      (node (ref "C21") (pin "2") (pinfunction "2_2") (pintype "passive"))
      (node (ref "C22") (pin "1") (pinfunction "1_1") (pintype "passive"))
      (node (ref "C23") (pin "1") (pinfunction "1_1") (pintype "passive"))
      (node (ref "C24") (pin "1") (pinfunction "1_1") (pintype "passive"))
      (node (ref "C25") (pin "1") (pinfunction "1_1") (pintype "passive"))
      (node (ref "C26") (pin "2") (pinfunction "2_2") (pintype "passive"))
      (node (ref "C27") (pin "1") (pinfunction "1_1") (pintype "passive"))
      (node (ref "C28") (pin "1") (pinfunction "1_1") (pintype "passive"))
      (node (ref "C29") (pin "1") (pinfunction "1_1") (pintype "passive"))
      (node (ref "C3") (pin "2") (pinfunction "2_2") (pintype "passive"))
      (node (ref "C30") (pin "1") (pinfunction "1_1") (pintype "passive"))
      (node (ref "C35") (pin "2") (pinfunction "2_2") (pintype "passive"))
      (node (ref "C36") (pin "2") (pinfunction "2_2") (pintype "passive"))
      (node (ref "C37") (pin "2") (pinfunction "2_2") (pintype "passive"))
      (node (ref "C38") (pin "2") (pinfunction "2_2") (pintype "passive"))
      (node (ref "C39") (pin "2") (pinfunction "2_2") (pintype "passive"))
      (node (ref "C4") (pin "2") (pinfunction "2_2") (pintype "passive"))
      (node (ref "C40") (pin "2") (pinfunction "2_2") (pintype "passive"))
      (node (ref "C41") (pin "2") (pinfunction "2_2") (pintype "passive"))
      (node (ref "C42") (pin "2") (pinfunction "2_2") (pintype "passive"))
      (node (ref "C43") (pin "2") (pinfunction "2_2") (pintype "passive"))
      (node (ref "C44") (pin "2") (pinfunction "2_2") (pintype "passive"))
      (node (ref "C45") (pin "2") (pinfunction "2_2") (pintype "passive"))
      (node (ref "C46") (pin "2") (pinfunction "2_2") (pintype "passive"))
      (node (ref "C47") (pin "2") (pinfunction "2_2") (pintype "passive"))
      (node (ref "C48") (pin "2") (pinfunction "2_2") (pintype "passive"))
      (node (ref "C5") (pin "2") (pinfunction "2_2") (pintype "passive"))
      (node (ref "C52") (pin "2") (pinfunction "2_2") (pintype "passive"))
      (node (ref "C53") (pin "2") (pinfunction "2_2") (pintype "passive"))
      (node (ref "C56") (pin "2") (pinfunction "2_2") (pintype "passive"))
      (node (ref "C57") (pin "2") (pinfunction "2_2") (pintype "passive"))
      (node (ref "C6") (pin "2") (pinfunction "2_2") (pintype "passive"))
      (node (ref "C61") (pin "2") (pinfunction "2_2") (pintype "passive"))
      (node (ref "C62") (pin "2") (pinfunction "2_2") (pintype "passive"))
      (node (ref "C65") (pin "1") (pinfunction "1_1") (pintype "passive"))
      (node (ref "C66") (pin "1") (pinfunction "1_1") (pintype "passive"))
      (node (ref "C67") (pin "1") (pinfunction "1_1") (pintype "passive"))
      (node (ref "C7") (pin "2") (pinfunction "2_2") (pintype "passive"))
      (node (ref "C70") (pin "1") (pinfunction "1_1") (pintype "passive"))
      (node (ref "C71") (pin "1") (pinfunction "1_1") (pintype "passive"))
      (node (ref "C72") (pin "1") (pinfunction "1_1") (pintype "passive"))
      (node (ref "C77") (pin "2") (pinfunction "2_2") (pintype "passive"))
      (node (ref "C78") (pin "1") (pinfunction "1_1") (pintype "passive"))
      (node (ref "C79") (pin "2") (pinfunction "2_2") (pintype "passive"))
      (node (ref "C8") (pin "2") (pinfunction "2_2") (pintype "passive"))
      (node (ref "C80") (pin "2") (pinfunction "2_2") (pintype "passive"))
      (node (ref "C81") (pin "2") (pinfunction "2_2") (pintype "passive"))
      (node (ref "C82") (pin "1") (pinfunction "1_1") (pintype "passive"))
      (node (ref "C83") (pin "1") (pinfunction "1_1") (pintype "passive"))
      (node (ref "C84") (pin "2") (pinfunction "2_2") (pintype "passive"))
      (node (ref "C9") (pin "2") (pinfunction "2_2") (pintype "passive"))
      (node (ref "D18") (pin "2") (pinfunction "CATHODE_2") (pintype "passive"))
      (node (ref "J17") (pin "0") (pinfunction "GND_0") (pintype "power_in"))
      (node (ref "J17") (pin "1") (pinfunction "1_1") (pintype "passive"))
      (node (ref "J17") (pin "3") (pinfunction "3_3") (pintype "passive"))
      (node (ref "J23") (pin "1") (pinfunction "1_1") (pintype "passive"))
      (node (ref "J25") (pin "1") (pinfunction "1_1") (pintype "passive"))
      (node (ref "LED3") (pin "4") (pinfunction "GND_4") (pintype "passive"))
      (node (ref "LED4") (pin "4") (pinfunction "GND_4") (pintype "passive"))
      (node (ref "LED5") (pin "4") (pinfunction "GND_4") (pintype "passive"))
      (node (ref "LED6") (pin "4") (pinfunction "GND_4") (pintype "passive"))
      (node (ref "Q19") (pin "3") (pinfunction "S_3") (pintype "passive"))
      (node (ref "Q20") (pin "3") (pinfunction "S_3") (pintype "passive"))
      (node (ref "Q7") (pin "3") (pinfunction "S_3") (pintype "passive"))
      (node (ref "Q8") (pin "3") (pinfunction "S_3") (pintype "passive"))
      (node (ref "R100") (pin "2") (pinfunction "2_2") (pintype "passive"))
      (node (ref "R101") (pin "2") (pinfunction "2_2") (pintype "passive"))
      (node (ref "R102") (pin "2") (pinfunction "2_2") (pintype "passive"))
      (node (ref "R103") (pin "2") (pinfunction "2_2") (pintype "passive"))
      (node (ref "R104") (pin "2") (pinfunction "2_2") (pintype "passive"))
      (node (ref "R105") (pin "2") (pinfunction "2_2") (pintype "passive"))
      (node (ref "R110") (pin "1") (pinfunction "1_1") (pintype "passive"))
      (node (ref "R111") (pin "1") (pinfunction "1_1") (pintype "passive"))
      (node (ref "R121") (pin "2") (pinfunction "2_2") (pintype "passive"))
      (node (ref "R122") (pin "2") (pinfunction "2_2") (pintype "passive"))
      (node (ref "R142") (pin "2") (pinfunction "2_2") (pintype "passive"))
      (node (ref "R15") (pin "1") (pinfunction "1_1") (pintype "passive"))
      (node (ref "R16") (pin "1") (pinfunction "1_1") (pintype "passive"))
      (node (ref "R17") (pin "1") (pinfunction "1_1") (pintype "passive"))
      (node (ref "R18") (pin "1") (pinfunction "1_1") (pintype "passive"))
      (node (ref "R21") (pin "2") (pinfunction "2_2") (pintype "passive"))
      (node (ref "R22") (pin "2") (pinfunction "2_2") (pintype "passive"))
      (node (ref "R29") (pin "2") (pinfunction "2_2") (pintype "passive"))
      (node (ref "R30") (pin "2") (pinfunction "2_2") (pintype "passive"))
      (node (ref "R31") (pin "2") (pinfunction "2_2") (pintype "passive"))
      (node (ref "R32") (pin "2") (pinfunction "2_2") (pintype "passive"))
      (node (ref "R37") (pin "1") (pinfunction "1_1") (pintype "passive"))
      (node (ref "R38") (pin "1") (pinfunction "1_1") (pintype "passive"))
      (node (ref "R48") (pin "2") (pinfunction "2_2") (pintype "passive"))
      (node (ref "R49") (pin "2") (pinfunction "2_2") (pintype "passive"))
      (node (ref "R83") (pin "1") (pinfunction "1_1") (pintype "passive"))
      (node (ref "R84") (pin "1") (pinfunction "1_1") (pintype "passive"))
      (node (ref "R85") (pin "1") (pinfunction "1_1") (pintype "passive"))
      (node (ref "R86") (pin "1") (pinfunction "1_1") (pintype "passive"))
      (node (ref "R89") (pin "2") (pinfunction "2_2") (pintype "passive"))
      (node (ref "R90") (pin "2") (pinfunction "2_2") (pintype "passive"))
      (node (ref "R99") (pin "2") (pinfunction "2_2") (pintype "passive"))
      (node (ref "U1") (pin "0") (pinfunction "VSSA_0") (pintype "power_in"))
      (node (ref "U1") (pin "14") (pinfunction "VSS_14") (pintype "passive"))
      (node (ref "U1") (pin "16") (pinfunction "VSS_16") (pintype "passive"))
      (node (ref "U1") (pin "32") (pinfunction "VSS_32") (pintype "passive"))
      (node (ref "U11") (pin "2") (pinfunction "GND_2") (pintype "passive"))
      (node (ref "U12") (pin "2") (pinfunction "GND_2") (pintype "passive"))
      (node (ref "U13") (pin "2") (pinfunction "GND_2") (pintype "passive"))
      (node (ref "U2") (pin "0") (pinfunction "NC_0") (pintype "passive"))
      (node (ref "U2") (pin "6") (pinfunction "GND_6") (pintype "passive"))
      (node (ref "U3") (pin "0") (pinfunction "VSSA_0") (pintype "power_in"))
      (node (ref "U3") (pin "14") (pinfunction "VSS_14") (pintype "passive"))
      (node (ref "U3") (pin "16") (pinfunction "VSS_16") (pintype "passive"))
      (node (ref "U3") (pin "32") (pinfunction "VSS_32") (pintype "passive"))
      (node (ref "U4") (pin "0") (pinfunction "NC_0") (pintype "passive"))
      (node (ref "U4") (pin "6") (pinfunction "GND_6") (pintype "passive"))
      (node (ref "U5") (pin "0") (pinfunction "VSSA_0") (pintype "power_in"))
      (node (ref "U5") (pin "14") (pinfunction "VSS_14") (pintype "passive"))
      (node (ref "U5") (pin "16") (pinfunction "VSS_16") (pintype "passive"))
      (node (ref "U5") (pin "32") (pinfunction "VSS_32") (pintype "passive"))
      (node (ref "U6") (pin "0") (pinfunction "NC_0") (pintype "passive"))
      (node (ref "U6") (pin "6") (pinfunction "GND_6") (pintype "passive"))
      (node (ref "U7") (pin "0") (pinfunction "VSSA_0") (pintype "power_in"))
      (node (ref "U7") (pin "14") (pinfunction "VSS_14") (pintype "passive"))
      (node (ref "U7") (pin "16") (pinfunction "VSS_16") (pintype "passive"))
      (node (ref "U7") (pin "32") (pinfunction "VSS_32") (pintype "passive"))
      (node (ref "U8") (pin "0") (pinfunction "NC_0") (pintype "passive"))
      (node (ref "U8") (pin "6") (pinfunction "GND_6") (pintype "passive"))
      (node (ref "U9") (pin "11") (pinfunction "GND_11") (pintype "passive"))
      (node (ref "U9") (pin "6") (pinfunction "GND_6") (pintype "passive"))
    )
    (net (code "51") (name "LED_1V") (class "Default")
      (node (ref "C21") (pin "1") (pinfunction "1_1") (pintype "passive"))
      (node (ref "LED3") (pin "2") (pinfunction "VDD_2") (pintype "passive"))
      (node (ref "LED6") (pin "2") (pinfunction "VDD_2") (pintype "passive"))
      (node (ref "U12") (pin "5") (pinfunction "VOUT_5") (pintype "passive"))
    )
    (net (code "52") (name "LED_2V") (class "Default")
      (node (ref "C26") (pin "1") (pinfunction "1_1") (pintype "passive"))
      (node (ref "LED4") (pin "2") (pinfunction "VDD_2") (pintype "passive"))
      (node (ref "LED5") (pin "2") (pinfunction "VDD_2") (pintype "passive"))
      (node (ref "U13") (pin "5") (pinfunction "VOUT_5") (pintype "passive"))
    )
    (net (code "53") (name "Net-(C11-Pad1)") (class "Default")
      (node (ref "C11") (pin "1") (pinfunction "1_1") (pintype "passive"))
      (node (ref "R13") (pin "1") (pinfunction "1_1") (pintype "passive"))
    )
    (net (code "54") (name "Net-(C12-Pad1)") (class "Default")
      (node (ref "C12") (pin "1") (pinfunction "1_1") (pintype "passive"))
      (node (ref "R14") (pin "1") (pinfunction "1_1") (pintype "passive"))
    )
    (net (code "55") (name "Net-(C19-Pad1)") (class "Default")
      (node (ref "C19") (pin "1") (pinfunction "1_1") (pintype "passive"))
      (node (ref "R27") (pin "1") (pinfunction "1_1") (pintype "passive"))
    )
    (net (code "56") (name "Net-(C20-Pad1)") (class "Default")
      (node (ref "C20") (pin "1") (pinfunction "1_1") (pintype "passive"))
      (node (ref "R28") (pin "1") (pinfunction "1_1") (pintype "passive"))
    )
    (net (code "57") (name "Net-(C35-Pad1)") (class "Default")
      (node (ref "C35") (pin "1") (pinfunction "1_1") (pintype "passive"))
      (node (ref "R45") (pin "1") (pinfunction "1_1") (pintype "passive"))
    )
    (net (code "58") (name "Net-(C36-Pad1)") (class "Default")
      (node (ref "C36") (pin "1") (pinfunction "1_1") (pintype "passive"))
      (node (ref "R46") (pin "1") (pinfunction "1_1") (pintype "passive"))
    )
    (net (code "59") (name "Net-(C47-Pad1)") (class "Default")
      (node (ref "C47") (pin "1") (pinfunction "1_1") (pintype "passive"))
      (node (ref "R81") (pin "1") (pinfunction "1_1") (pintype "passive"))
    )
    (net (code "60") (name "Net-(C48-Pad1)") (class "Default")
      (node (ref "C48") (pin "1") (pinfunction "1_1") (pintype "passive"))
      (node (ref "R82") (pin "1") (pinfunction "1_1") (pintype "passive"))
    )
    (net (code "61") (name "Net-(C58-Pad1)") (class "Default")
      (node (ref "C58") (pin "1") (pinfunction "1_1") (pintype "passive"))
      (node (ref "R103") (pin "1") (pinfunction "1_1") (pintype "passive"))
    )
    (net (code "62") (name "Net-(C61-Pad1)") (class "Default")
      (node (ref "C61") (pin "1") (pinfunction "1_1") (pintype "passive"))
      (node (ref "R97") (pin "1") (pinfunction "1_1") (pintype "passive"))
    )
    (net (code "63") (name "Net-(C62-Pad1)") (class "Default")
      (node (ref "C62") (pin "1") (pinfunction "1_1") (pintype "passive"))
      (node (ref "R98") (pin "1") (pinfunction "1_1") (pintype "passive"))
    )
    (net (code "64") (name "Net-(C80-Pad1)") (class "Default")
      (node (ref "C80") (pin "1") (pinfunction "1_1") (pintype "passive"))
      (node (ref "R118") (pin "1") (pinfunction "1_1") (pintype "passive"))
    )
    (net (code "65") (name "Net-(C81-Pad1)") (class "Default")
      (node (ref "C81") (pin "1") (pinfunction "1_1") (pintype "passive"))
      (node (ref "R119") (pin "1") (pinfunction "1_1") (pintype "passive"))
    )
    (net (code "66") (name "Net-(D7-Pad2)") (class "Default")
      (node (ref "D7") (pin "2") (pinfunction "2_2") (pintype "passive"))
      (node (ref "R56") (pin "1") (pinfunction "1_1") (pintype "passive"))
    )
    (net (code "67") (name "Net-(D8-Pad2)") (class "Default")
      (node (ref "D8") (pin "2") (pinfunction "2_2") (pintype "passive"))
      (node (ref "R57") (pin "1") (pinfunction "1_1") (pintype "passive"))
    )
    (net (code "68") (name "Net-(D9-Pad2)") (class "Default")
      (node (ref "D9") (pin "2") (pinfunction "2_2") (pintype "passive"))
      (node (ref "R58") (pin "1") (pinfunction "1_1") (pintype "passive"))
    )
    (net (code "69") (name "Net-(D10-Pad2)") (class "Default")
      (node (ref "D10") (pin "2") (pinfunction "2_2") (pintype "passive"))
      (node (ref "R60") (pin "1") (pinfunction "1_1") (pintype "passive"))
    )
    (net (code "70") (name "Net-(D11-Pad2)") (class "Default")
      (node (ref "D11") (pin "2") (pinfunction "2_2") (pintype "passive"))
      (node (ref "R61") (pin "1") (pinfunction "1_1") (pintype "passive"))
    )
    (net (code "71") (name "Net-(D12-Pad2)") (class "Default")
      (node (ref "D12") (pin "2") (pinfunction "2_2") (pintype "passive"))
      (node (ref "R62") (pin "1") (pinfunction "1_1") (pintype "passive"))
    )
    (net (code "72") (name "Net-(D15-ANODE)") (class "Default")
      (node (ref "C52") (pin "1") (pinfunction "1_1") (pintype "passive"))
      (node (ref "C53") (pin "1") (pinfunction "1_1") (pintype "passive"))
      (node (ref "C84") (pin "1") (pinfunction "1_1") (pintype "passive"))
      (node (ref "D15") (pin "1") (pinfunction "ANODE_1") (pintype "passive"))
      (node (ref "R91") (pin "1") (pinfunction "1_1") (pintype "passive"))
      (node (ref "U9") (pin "8") (pinfunction "VIN_8") (pintype "passive"))
      (node (ref "U9") (pin "9") (pinfunction "VIN_9") (pintype "passive"))
    )
    (net (code "73") (name "Net-(D18-ANODE)") (class "Default")
      (node (ref "C51") (pin "1") (pinfunction "1_1") (pintype "passive"))
      (node (ref "D18") (pin "1") (pinfunction "ANODE_1") (pintype "passive"))
      (node (ref "L1") (pin "2") (pinfunction "2_2") (pintype "passive"))
      (node (ref "U9") (pin "1") (pinfunction "SW_1") (pintype "passive"))
      (node (ref "U9") (pin "2") (pinfunction "SW_2") (pintype "passive"))
    )
    (net (code "74") (name "Net-(D21-Pad2)") (class "Default")
      (node (ref "D21") (pin "2") (pinfunction "2_2") (pintype "passive"))
      (node (ref "R130") (pin "1") (pinfunction "1_1") (pintype "passive"))
    )
    (net (code "75") (name "Net-(D22-Pad2)") (class "Default")
      (node (ref "D22") (pin "2") (pinfunction "2_2") (pintype "passive"))
      (node (ref "R131") (pin "1") (pinfunction "1_1") (pintype "passive"))
    )
    (net (code "76") (name "Net-(D23-Pad2)") (class "Default")
      (node (ref "D23") (pin "2") (pinfunction "2_2") (pintype "passive"))
      (node (ref "R132") (pin "1") (pinfunction "1_1") (pintype "passive"))
    )
    (net (code "77") (name "Net-(D24-Pad2)") (class "Default")
      (node (ref "D24") (pin "2") (pinfunction "2_2") (pintype "passive"))
      (node (ref "R133") (pin "1") (pinfunction "1_1") (pintype "passive"))
    )
    (net (code "78") (name "Net-(D25-Pad2)") (class "Default")
      (node (ref "D25") (pin "2") (pinfunction "2_2") (pintype "passive"))
      (node (ref "R134") (pin "1") (pinfunction "1_1") (pintype "passive"))
    )
    (net (code "79") (name "Net-(D26-Pad2)") (class "Default")
      (node (ref "D26") (pin "2") (pinfunction "2_2") (pintype "passive"))
      (node (ref "R135") (pin "1") (pinfunction "1_1") (pintype "passive"))
    )
    (net (code "80") (name "Net-(LED1-Pad2)") (class "Default")
      (node (ref "LED1") (pin "2") (pinfunction "2_2") (pintype "passive"))
      (node (ref "R142") (pin "1") (pinfunction "1_1") (pintype "passive"))
    )
    (net (code "81") (name "Net-(LED3-DIN)") (class "Default")
      (node (ref "LED3") (pin "1") (pinfunction "DIN_1") (pintype "passive"))
      (node (ref "U5") (pin "29") (pinfunction "PB6-PWM_IN_29") (pintype "passive"))
    )
    (net (code "82") (name "Net-(LED4-DIN)") (class "Default")
      (node (ref "LED4") (pin "1") (pinfunction "DIN_1") (pintype "passive"))
      (node (ref "U1") (pin "29") (pinfunction "PB6-PWM_IN_29") (pintype "passive"))
    )
    (net (code "83") (name "Net-(LED5-DIN)") (class "Default")
      (node (ref "LED5") (pin "1") (pinfunction "DIN_1") (pintype "passive"))
      (node (ref "U3") (pin "29") (pinfunction "PB6-PWM_IN_29") (pintype "passive"))
    )
    (net (code "84") (name "Net-(LED6-DIN)") (class "Default")
      (node (ref "LED6") (pin "1") (pinfunction "DIN_1") (pintype "passive"))
      (node (ref "U7") (pin "29") (pinfunction "PB6-PWM_IN_29") (pintype "passive"))
    )
    (net (code "85") (name "Net-(Q1-G)") (class "Default")
      (node (ref "Q1") (pin "4") (pinfunction "G_4") (pintype "passive"))
      (node (ref "R5") (pin "2") (pinfunction "2_2") (pintype "passive"))
    )
    (net (code "86") (name "Net-(Q2-G)") (class "Default")
      (node (ref "Q2") (pin "4") (pinfunction "G_4") (pintype "passive"))
      (node (ref "R6") (pin "2") (pinfunction "2_2") (pintype "passive"))
    )
    (net (code "87") (name "Net-(Q3-G)") (class "Default")
      (node (ref "Q3") (pin "4") (pinfunction "G_4") (pintype "passive"))
      (node (ref "R10") (pin "2") (pinfunction "2_2") (pintype "passive"))
      (node (ref "R19") (pin "1") (pinfunction "1_1") (pintype "passive"))
    )
    (net (code "88") (name "Net-(Q3-S)") (class "Default")
      (node (ref "Q3") (pin "3") (pinfunction "S_3") (pintype "passive"))
      (node (ref "R19") (pin "2") (pinfunction "2_2") (pintype "passive"))
      (node (ref "R21") (pin "1") (pinfunction "1_1") (pintype "passive"))
    )
    (net (code "89") (name "Net-(Q4-G)") (class "Default")
      (node (ref "Q4") (pin "4") (pinfunction "G_4") (pintype "passive"))
      (node (ref "R12") (pin "2") (pinfunction "2_2") (pintype "passive"))
      (node (ref "R20") (pin "1") (pinfunction "1_1") (pintype "passive"))
    )
    (net (code "90") (name "Net-(Q4-S)") (class "Default")
      (node (ref "Q4") (pin "3") (pinfunction "S_3") (pintype "passive"))
      (node (ref "R20") (pin "2") (pinfunction "2_2") (pintype "passive"))
      (node (ref "R22") (pin "1") (pinfunction "1_1") (pintype "passive"))
    )
    (net (code "91") (name "Net-(Q5-G)") (class "Default")
      (node (ref "Q5") (pin "4") (pinfunction "G_4") (pintype "passive"))
      (node (ref "R23") (pin "2") (pinfunction "2_2") (pintype "passive"))
    )
    (net (code "92") (name "Net-(Q6-G)") (class "Default")
      (node (ref "Q6") (pin "4") (pinfunction "G_4") (pintype "passive"))
      (node (ref "R24") (pin "2") (pinfunction "2_2") (pintype "passive"))
    )
    (net (code "93") (name "Net-(Q7-G)") (class "Default")
      (node (ref "Q7") (pin "4") (pinfunction "G_4") (pintype "passive"))
      (node (ref "R25") (pin "2") (pinfunction "2_2") (pintype "passive"))
      (node (ref "R29") (pin "1") (pinfunction "1_1") (pintype "passive"))
    )
    (net (code "94") (name "Net-(Q8-G)") (class "Default")
      (node (ref "Q8") (pin "4") (pinfunction "G_4") (pintype "passive"))
      (node (ref "R26") (pin "2") (pinfunction "2_2") (pintype "passive"))
      (node (ref "R30") (pin "1") (pinfunction "1_1") (pintype "passive"))
    )
    (net (code "95") (name "Net-(Q9-G)") (class "Default")
      (node (ref "Q9") (pin "4") (pinfunction "G_4") (pintype "passive"))
      (node (ref "R41") (pin "2") (pinfunction "2_2") (pintype "passive"))
    )
    (net (code "96") (name "Net-(Q10-G)") (class "Default")
      (node (ref "Q10") (pin "4") (pinfunction "G_4") (pintype "passive"))
      (node (ref "R42") (pin "2") (pinfunction "2_2") (pintype "passive"))
    )
    (net (code "97") (name "Net-(Q11-G)") (class "Default")
      (node (ref "Q11") (pin "4") (pinfunction "G_4") (pintype "passive"))
      (node (ref "R43") (pin "2") (pinfunction "2_2") (pintype "passive"))
      (node (ref "R50") (pin "1") (pinfunction "1_1") (pintype "passive"))
    )
    (net (code "98") (name "Net-(Q11-S)") (class "Default")
      (node (ref "Q11") (pin "3") (pinfunction "S_3") (pintype "passive"))
      (node (ref "R31") (pin "1") (pinfunction "1_1") (pintype "passive"))
      (node (ref "R50") (pin "2") (pinfunction "2_2") (pintype "passive"))
    )
    (net (code "99") (name "Net-(Q12-G)") (class "Default")
      (node (ref "Q12") (pin "4") (pinfunction "G_4") (pintype "passive"))
      (node (ref "R44") (pin "2") (pinfunction "2_2") (pintype "passive"))
      (node (ref "R52") (pin "1") (pinfunction "1_1") (pintype "passive"))
    )
    (net (code "100") (name "Net-(Q12-S)") (class "Default")
      (node (ref "Q12") (pin "3") (pinfunction "S_3") (pintype "passive"))
      (node (ref "R32") (pin "1") (pinfunction "1_1") (pintype "passive"))
      (node (ref "R52") (pin "2") (pinfunction "2_2") (pintype "passive"))
    )
    (net (code "101") (name "Net-(Q13-G)") (class "Default")
      (node (ref "Q13") (pin "4") (pinfunction "G_4") (pintype "passive"))
      (node (ref "R73") (pin "2") (pinfunction "2_2") (pintype "passive"))
    )
    (net (code "102") (name "Net-(Q14-G)") (class "Default")
      (node (ref "Q14") (pin "4") (pinfunction "G_4") (pintype "passive"))
      (node (ref "R74") (pin "2") (pinfunction "2_2") (pintype "passive"))
    )
    (net (code "103") (name "Net-(Q15-G)") (class "Default")
      (node (ref "Q15") (pin "4") (pinfunction "G_4") (pintype "passive"))
      (node (ref "R78") (pin "2") (pinfunction "2_2") (pintype "passive"))
      (node (ref "R87") (pin "1") (pinfunction "1_1") (pintype "passive"))
    )
    (net (code "104") (name "Net-(Q15-S)") (class "Default")
      (node (ref "Q15") (pin "3") (pinfunction "S_3") (pintype "passive"))
      (node (ref "R87") (pin "2") (pinfunction "2_2") (pintype "passive"))
      (node (ref "R89") (pin "1") (pinfunction "1_1") (pintype "passive"))
    )
    (net (code "105") (name "Net-(Q16-G)") (class "Default")
      (node (ref "Q16") (pin "4") (pinfunction "G_4") (pintype "passive"))
      (node (ref "R80") (pin "2") (pinfunction "2_2") (pintype "passive"))
      (node (ref "R88") (pin "1") (pinfunction "1_1") (pintype "passive"))
    )
    (net (code "106") (name "Net-(Q16-S)") (class "Default")
      (node (ref "Q16") (pin "3") (pinfunction "S_3") (pintype "passive"))
      (node (ref "R88") (pin "2") (pinfunction "2_2") (pintype "passive"))
      (node (ref "R90") (pin "1") (pinfunction "1_1") (pintype "passive"))
    )
    (net (code "107") (name "Net-(Q17-G)") (class "Default")
      (node (ref "Q17") (pin "4") (pinfunction "G_4") (pintype "passive"))
      (node (ref "R93") (pin "2") (pinfunction "2_2") (pintype "passive"))
    )
    (net (code "108") (name "Net-(Q18-G)") (class "Default")
      (node (ref "Q18") (pin "4") (pinfunction "G_4") (pintype "passive"))
      (node (ref "R94") (pin "2") (pinfunction "2_2") (pintype "passive"))
    )
    (net (code "109") (name "Net-(Q19-G)") (class "Default")
      (node (ref "Q19") (pin "4") (pinfunction "G_4") (pintype "passive"))
      (node (ref "R100") (pin "1") (pinfunction "1_1") (pintype "passive"))
      (node (ref "R95") (pin "2") (pinfunction "2_2") (pintype "passive"))
    )
    (net (code "110") (name "Net-(Q20-G)") (class "Default")
      (node (ref "Q20") (pin "4") (pinfunction "G_4") (pintype "passive"))
      (node (ref "R101") (pin "1") (pinfunction "1_1") (pintype "passive"))
      (node (ref "R96") (pin "2") (pinfunction "2_2") (pintype "passive"))
    )
    (net (code "111") (name "Net-(Q21-G)") (class "Default")
      (node (ref "Q21") (pin "4") (pinfunction "G_4") (pintype "passive"))
      (node (ref "R114") (pin "2") (pinfunction "2_2") (pintype "passive"))
    )
    (net (code "112") (name "Net-(Q22-G)") (class "Default")
      (node (ref "Q22") (pin "4") (pinfunction "G_4") (pintype "passive"))
      (node (ref "R115") (pin "2") (pinfunction "2_2") (pintype "passive"))
    )
    (net (code "113") (name "Net-(Q23-G)") (class "Default")
      (node (ref "Q23") (pin "4") (pinfunction "G_4") (pintype "passive"))
      (node (ref "R116") (pin "2") (pinfunction "2_2") (pintype "passive"))
      (node (ref "R124") (pin "1") (pinfunction "1_1") (pintype "passive"))
    )
    (net (code "114") (name "Net-(Q23-S)") (class "Default")
      (node (ref "Q23") (pin "3") (pinfunction "S_3") (pintype "passive"))
      (node (ref "R104") (pin "1") (pinfunction "1_1") (pintype "passive"))
      (node (ref "R124") (pin "2") (pinfunction "2_2") (pintype "passive"))
    )
    (net (code "115") (name "Net-(Q24-G)") (class "Default")
      (node (ref "Q24") (pin "4") (pinfunction "G_4") (pintype "passive"))
      (node (ref "R117") (pin "2") (pinfunction "2_2") (pintype "passive"))
      (node (ref "R125") (pin "1") (pinfunction "1_1") (pintype "passive"))
    )
    (net (code "116") (name "Net-(Q24-S)") (class "Default")
      (node (ref "Q24") (pin "3") (pinfunction "S_3") (pintype "passive"))
      (node (ref "R105") (pin "1") (pinfunction "1_1") (pintype "passive"))
      (node (ref "R125") (pin "2") (pinfunction "2_2") (pintype "passive"))
    )
    (net (code "117") (name "Net-(U1-BOOT0{slash}PB8)") (class "Default")
      (node (ref "R48") (pin "1") (pinfunction "1_1") (pintype "passive"))
      (node (ref "U1") (pin "31") (pinfunction "BOOT0/PB8_31") (pintype "passive"))
    )
    (net (code "118") (name "Net-(U1-NRST)") (class "Default")
      (node (ref "R39") (pin "2") (pinfunction "2_2") (pintype "passive"))
      (node (ref "U1") (pin "4") (pinfunction "NRST_4") (pintype "passive"))
    )
    (net (code "119") (name "Net-(U1-PA0-V-BUS)") (class "Default")
      (node (ref "R33") (pin "1") (pinfunction "1_1") (pintype "passive"))
      (node (ref "R37") (pin "2") (pinfunction "2_2") (pintype "passive"))
      (node (ref "U1") (pin "5") (pinfunction "PA0-V-BUS_5") (pintype "passive"))
    )
    (net (code "120") (name "Net-(U1-PA4-BEMF1)") (class "Default")
      (node (ref "R47") (pin "2") (pinfunction "2_2") (pintype "passive"))
      (node (ref "R56") (pin "2") (pinfunction "2_2") (pintype "passive"))
      (node (ref "R63") (pin "2") (pinfunction "2_2") (pintype "passive"))
      (node (ref "U1") (pin "9") (pinfunction "PA4-BEMF1_9") (pintype "passive"))
    )
    (net (code "121") (name "Net-(U1-PA8-TIM1_CH1)") (class "Default")
      (node (ref "U1") (pin "18") (pinfunction "PA8-TIM1_CH1_18") (pintype "passive"))
      (node (ref "U2") (pin "22") (pinfunction "HIN1_22") (pintype "passive"))
    )
    (net (code "122") (name "Net-(U1-PA9--TIM1_CH2)") (class "Default")
      (node (ref "U1") (pin "19") (pinfunction "PA9--TIM1_CH2_19") (pintype "passive"))
      (node (ref "U2") (pin "23") (pinfunction "HIN2_23") (pintype "passive"))
    )
    (net (code "123") (name "Net-(U1-PA10-TIM1_CH3)") (class "Default")
      (node (ref "U1") (pin "20") (pinfunction "PA10-TIM1_CH3_20") (pintype "passive"))
      (node (ref "U2") (pin "24") (pinfunction "HIN3_24") (pintype "passive"))
    )
    (net (code "124") (name "Net-(U1-PA11-TIM1_CH1N)") (class "Default")
      (node (ref "U1") (pin "21") (pinfunction "PA11-TIM1_CH1N_21") (pintype "passive"))
      (node (ref "U2") (pin "1") (pinfunction "LIN1_1") (pintype "passive"))
    )
    (net (code "125") (name "Net-(U1-PA12-TIM1_CH2N)") (class "Default")
      (node (ref "U1") (pin "22") (pinfunction "PA12-TIM1_CH2N_22") (pintype "passive"))
      (node (ref "U2") (pin "2") (pinfunction "LIN2_2") (pintype "passive"))
    )
    (net (code "126") (name "Net-(U1-PA13-LED_BLUE-SWDIO)") (class "Default")
      (node (ref "J7") (pin "1") (pinfunction "1_1") (pintype "passive"))
      (node (ref "U1") (pin "23") (pinfunction "PA13-LED_BLUE-SWDIO_23") (pintype "passive"))
    )
    (net (code "127") (name "Net-(U1-PA14-LED_GREE-SWCLK)") (class "Default")
      (node (ref "J9") (pin "1") (pinfunction "1_1") (pintype "passive"))
      (node (ref "U1") (pin "24") (pinfunction "PA14-LED_GREE-SWCLK_24") (pintype "passive"))
    )
    (net (code "128") (name "Net-(U1-PA15-SPI1_NSS)") (class "Default")
      (node (ref "R35") (pin "1") (pinfunction "1_1") (pintype "passive"))
      (node (ref "U1") (pin "25") (pinfunction "PA15-SPI1_NSS_25") (pintype "passive"))
    )
    (net (code "129") (name "Net-(U1-PB0--BEMF2)") (class "Default")
      (node (ref "R53") (pin "2") (pinfunction "2_2") (pintype "passive"))
      (node (ref "R57") (pin "2") (pinfunction "2_2") (pintype "passive"))
      (node (ref "R64") (pin "2") (pinfunction "2_2") (pintype "passive"))
      (node (ref "U1") (pin "13") (pinfunction "PB0--BEMF2_13") (pintype "passive"))
    )
    (net (code "130") (name "Net-(U1-PB3-SPI1_SCK)") (class "Default")
      (node (ref "R147") (pin "1") (pinfunction "1_1") (pintype "passive"))
      (node (ref "U1") (pin "26") (pinfunction "PB3-SPI1_SCK_26") (pintype "passive"))
    )
    (net (code "131") (name "Net-(U1-PB4-SPI1_MISO)") (class "Default")
      (node (ref "R143") (pin "1") (pinfunction "1_1") (pintype "passive"))
      (node (ref "U1") (pin "27") (pinfunction "PB4-SPI1_MISO_27") (pintype "passive"))
    )
    (net (code "132") (name "Net-(U1-PB5-SPI1_MOSI)") (class "Default")
      (node (ref "R145") (pin "1") (pinfunction "1_1") (pintype "passive"))
      (node (ref "U1") (pin "28") (pinfunction "PB5-SPI1_MOSI_28") (pintype "passive"))
    )
    (net (code "133") (name "Net-(U1-PF0-TIM1_CH3N)") (class "Default")
      (node (ref "U1") (pin "2") (pinfunction "PF0-TIM1_CH3N_2") (pintype "passive"))
      (node (ref "U2") (pin "3") (pinfunction "LIN3_3") (pintype "passive"))
    )
    (net (code "134") (name "Net-(U1-PF1--BEMF3)") (class "Default")
      (node (ref "R55") (pin "2") (pinfunction "2_2") (pintype "passive"))
      (node (ref "R58") (pin "2") (pinfunction "2_2") (pintype "passive"))
      (node (ref "R65") (pin "2") (pinfunction "2_2") (pintype "passive"))
      (node (ref "U1") (pin "3") (pinfunction "PF1--BEMF3_3") (pintype "passive"))
    )
    (net (code "135") (name "Net-(U2-HO1)") (class "Default")
      (node (ref "R5") (pin "1") (pinfunction "1_1") (pintype "passive"))
      (node (ref "U2") (pin "19") (pinfunction "HO1_19") (pintype "passive"))
    )
    (net (code "136") (name "Net-(U2-HO2)") (class "Default")
      (node (ref "R23") (pin "1") (pinfunction "1_1") (pintype "passive"))
      (node (ref "U2") (pin "16") (pinfunction "HO2_16") (pintype "passive"))
    )
    (net (code "137") (name "Net-(U2-HO3)") (class "Default")
      (node (ref "R41") (pin "1") (pinfunction "1_1") (pintype "passive"))
      (node (ref "U2") (pin "13") (pinfunction "HO3_13") (pintype "passive"))
    )
    (net (code "138") (name "Net-(U2-LO1)") (class "Default")
      (node (ref "R10") (pin "1") (pinfunction "1_1") (pintype "passive"))
      (node (ref "U2") (pin "11") (pinfunction "LO1_11") (pintype "passive"))
    )
    (net (code "139") (name "Net-(U2-LO2)") (class "Default")
      (node (ref "R25") (pin "1") (pinfunction "1_1") (pintype "passive"))
      (node (ref "U2") (pin "10") (pinfunction "LO2_10") (pintype "passive"))
    )
    (net (code "140") (name "Net-(U2-LO3)") (class "Default")
      (node (ref "R43") (pin "1") (pinfunction "1_1") (pintype "passive"))
      (node (ref "U2") (pin "9") (pinfunction "LO3_9") (pintype "passive"))
    )
    (net (code "141") (name "Net-(U2-VB1)") (class "Default")
      (node (ref "C13") (pin "2") (pinfunction "2_2") (pintype "passive"))
      (node (ref "D1") (pin "1") (pinfunction "1_1") (pintype "passive"))
      (node (ref "U2") (pin "20") (pinfunction "VB1_20") (pintype "passive"))
    )
    (net (code "142") (name "Net-(U2-VB2)") (class "Default")
      (node (ref "C15") (pin "2") (pinfunction "2_2") (pintype "passive"))
      (node (ref "D3") (pin "1") (pinfunction "1_1") (pintype "passive"))
      (node (ref "U2") (pin "17") (pinfunction "VB2_17") (pintype "passive"))
    )
    (net (code "143") (name "Net-(U2-VB3)") (class "Default")
      (node (ref "C17") (pin "2") (pinfunction "2_2") (pintype "passive"))
      (node (ref "D5") (pin "1") (pinfunction "1_1") (pintype "passive"))
      (node (ref "U2") (pin "14") (pinfunction "VB3_14") (pintype "passive"))
    )
    (net (code "144") (name "Net-(U3-BOOT0{slash}PB8)") (class "Default")
      (node (ref "R49") (pin "1") (pinfunction "1_1") (pintype "passive"))
      (node (ref "U3") (pin "31") (pinfunction "BOOT0/PB8_31") (pintype "passive"))
    )
    (net (code "145") (name "Net-(U3-NRST)") (class "Default")
      (node (ref "R40") (pin "2") (pinfunction "2_2") (pintype "passive"))
      (node (ref "U3") (pin "4") (pinfunction "NRST_4") (pintype "passive"))
    )
    (net (code "146") (name "Net-(U3-PA0-V-BUS)") (class "Default")
      (node (ref "R34") (pin "1") (pinfunction "1_1") (pintype "passive"))
      (node (ref "R38") (pin "2") (pinfunction "2_2") (pintype "passive"))
      (node (ref "U3") (pin "5") (pinfunction "PA0-V-BUS_5") (pintype "passive"))
    )
    (net (code "147") (name "Net-(U3-PA4-BEMF1)") (class "Default")
      (node (ref "R51") (pin "2") (pinfunction "2_2") (pintype "passive"))
      (node (ref "R60") (pin "2") (pinfunction "2_2") (pintype "passive"))
      (node (ref "R66") (pin "2") (pinfunction "2_2") (pintype "passive"))
      (node (ref "U3") (pin "9") (pinfunction "PA4-BEMF1_9") (pintype "passive"))
    )
    (net (code "148") (name "Net-(U3-PA8-TIM1_CH1)") (class "Default")
      (node (ref "U3") (pin "18") (pinfunction "PA8-TIM1_CH1_18") (pintype "passive"))
      (node (ref "U4") (pin "22") (pinfunction "HIN1_22") (pintype "passive"))
    )
    (net (code "149") (name "Net-(U3-PA9--TIM1_CH2)") (class "Default")
      (node (ref "U3") (pin "19") (pinfunction "PA9--TIM1_CH2_19") (pintype "passive"))
      (node (ref "U4") (pin "23") (pinfunction "HIN2_23") (pintype "passive"))
    )
    (net (code "150") (name "Net-(U3-PA10-TIM1_CH3)") (class "Default")
      (node (ref "U3") (pin "20") (pinfunction "PA10-TIM1_CH3_20") (pintype "passive"))
      (node (ref "U4") (pin "24") (pinfunction "HIN3_24") (pintype "passive"))
    )
    (net (code "151") (name "Net-(U3-PA11-TIM1_CH1N)") (class "Default")
      (node (ref "U3") (pin "21") (pinfunction "PA11-TIM1_CH1N_21") (pintype "passive"))
      (node (ref "U4") (pin "1") (pinfunction "LIN1_1") (pintype "passive"))
    )
    (net (code "152") (name "Net-(U3-PA12-TIM1_CH2N)") (class "Default")
      (node (ref "U3") (pin "22") (pinfunction "PA12-TIM1_CH2N_22") (pintype "passive"))
      (node (ref "U4") (pin "2") (pinfunction "LIN2_2") (pintype "passive"))
    )
    (net (code "153") (name "Net-(U3-PA13-LED_BLUE-SWDIO)") (class "Default")
      (node (ref "J8") (pin "1") (pinfunction "1_1") (pintype "passive"))
      (node (ref "U3") (pin "23") (pinfunction "PA13-LED_BLUE-SWDIO_23") (pintype "passive"))
    )
    (net (code "154") (name "Net-(U3-PA14-LED_GREE-SWCLK)") (class "Default")
      (node (ref "J10") (pin "1") (pinfunction "1_1") (pintype "passive"))
      (node (ref "U3") (pin "24") (pinfunction "PA14-LED_GREE-SWCLK_24") (pintype "passive"))
    )
    (net (code "155") (name "Net-(U3-PA15-SPI1_NSS)") (class "Default")
      (node (ref "R36") (pin "1") (pinfunction "1_1") (pintype "passive"))
      (node (ref "U3") (pin "25") (pinfunction "PA15-SPI1_NSS_25") (pintype "passive"))
    )
    (net (code "156") (name "Net-(U3-PB0--BEMF2)") (class "Default")
      (node (ref "R54") (pin "2") (pinfunction "2_2") (pintype "passive"))
      (node (ref "R61") (pin "2") (pinfunction "2_2") (pintype "passive"))
      (node (ref "R67") (pin "2") (pinfunction "2_2") (pintype "passive"))
      (node (ref "U3") (pin "13") (pinfunction "PB0--BEMF2_13") (pintype "passive"))
    )
    (net (code "157") (name "Net-(U3-PB3-SPI1_SCK)") (class "Default")
      (node (ref "R148") (pin "1") (pinfunction "1_1") (pintype "passive"))
      (node (ref "U3") (pin "26") (pinfunction "PB3-SPI1_SCK_26") (pintype "passive"))
    )
    (net (code "158") (name "Net-(U3-PB4-SPI1_MISO)") (class "Default")
      (node (ref "R144") (pin "1") (pinfunction "1_1") (pintype "passive"))
      (node (ref "U3") (pin "27") (pinfunction "PB4-SPI1_MISO_27") (pintype "passive"))
    )
    (net (code "159") (name "Net-(U3-PB5-SPI1_MOSI)") (class "Default")
      (node (ref "R146") (pin "1") (pinfunction "1_1") (pintype "passive"))
      (node (ref "U3") (pin "28") (pinfunction "PB5-SPI1_MOSI_28") (pintype "passive"))
    )
    (net (code "160") (name "Net-(U3-PF0-TIM1_CH3N)") (class "Default")
      (node (ref "U3") (pin "2") (pinfunction "PF0-TIM1_CH3N_2") (pintype "passive"))
      (node (ref "U4") (pin "3") (pinfunction "LIN3_3") (pintype "passive"))
    )
    (net (code "161") (name "Net-(U3-PF1--BEMF3)") (class "Default")
      (node (ref "R59") (pin "2") (pinfunction "2_2") (pintype "passive"))
      (node (ref "R62") (pin "2") (pinfunction "2_2") (pintype "passive"))
      (node (ref "R68") (pin "2") (pinfunction "2_2") (pintype "passive"))
      (node (ref "U3") (pin "3") (pinfunction "PF1--BEMF3_3") (pintype "passive"))
    )
    (net (code "162") (name "Net-(U4-HO1)") (class "Default")
      (node (ref "R6") (pin "1") (pinfunction "1_1") (pintype "passive"))
      (node (ref "U4") (pin "19") (pinfunction "HO1_19") (pintype "passive"))
    )
    (net (code "163") (name "Net-(U4-HO2)") (class "Default")
      (node (ref "R24") (pin "1") (pinfunction "1_1") (pintype "passive"))
      (node (ref "U4") (pin "16") (pinfunction "HO2_16") (pintype "passive"))
    )
    (net (code "164") (name "Net-(U4-HO3)") (class "Default")
      (node (ref "R42") (pin "1") (pinfunction "1_1") (pintype "passive"))
      (node (ref "U4") (pin "13") (pinfunction "HO3_13") (pintype "passive"))
    )
    (net (code "165") (name "Net-(U4-LO1)") (class "Default")
      (node (ref "R12") (pin "1") (pinfunction "1_1") (pintype "passive"))
      (node (ref "U4") (pin "11") (pinfunction "LO1_11") (pintype "passive"))
    )
    (net (code "166") (name "Net-(U4-LO2)") (class "Default")
      (node (ref "R26") (pin "1") (pinfunction "1_1") (pintype "passive"))
      (node (ref "U4") (pin "10") (pinfunction "LO2_10") (pintype "passive"))
    )
    (net (code "167") (name "Net-(U4-LO3)") (class "Default")
      (node (ref "R44") (pin "1") (pinfunction "1_1") (pintype "passive"))
      (node (ref "U4") (pin "9") (pinfunction "LO3_9") (pintype "passive"))
    )
    (net (code "168") (name "Net-(U4-VB1)") (class "Default")
      (node (ref "C14") (pin "2") (pinfunction "2_2") (pintype "passive"))
      (node (ref "D2") (pin "1") (pinfunction "1_1") (pintype "passive"))
      (node (ref "U4") (pin "20") (pinfunction "VB1_20") (pintype "passive"))
    )
    (net (code "169") (name "Net-(U4-VB2)") (class "Default")
      (node (ref "C16") (pin "2") (pinfunction "2_2") (pintype "passive"))
      (node (ref "D4") (pin "1") (pinfunction "1_1") (pintype "passive"))
      (node (ref "U4") (pin "17") (pinfunction "VB2_17") (pintype "passive"))
    )
    (net (code "170") (name "Net-(U4-VB3)") (class "Default")
      (node (ref "C18") (pin "2") (pinfunction "2_2") (pintype "passive"))
      (node (ref "D6") (pin "1") (pinfunction "1_1") (pintype "passive"))
      (node (ref "U4") (pin "14") (pinfunction "VB3_14") (pintype "passive"))
    )
    (net (code "171") (name "Net-(U5-BOOT0{slash}PB8)") (class "Default")
      (node (ref "R121") (pin "1") (pinfunction "1_1") (pintype "passive"))
      (node (ref "U5") (pin "31") (pinfunction "BOOT0/PB8_31") (pintype "passive"))
    )
    (net (code "172") (name "Net-(U5-NRST)") (class "Default")
      (node (ref "R112") (pin "2") (pinfunction "2_2") (pintype "passive"))
      (node (ref "U5") (pin "4") (pinfunction "NRST_4") (pintype "passive"))
    )
    (net (code "173") (name "Net-(U5-PA0-V-BUS)") (class "Default")
      (node (ref "R106") (pin "1") (pinfunction "1_1") (pintype "passive"))
      (node (ref "R110") (pin "2") (pinfunction "2_2") (pintype "passive"))
      (node (ref "U5") (pin "5") (pinfunction "PA0-V-BUS_5") (pintype "passive"))
    )
    (net (code "174") (name "Net-(U5-PA4-BEMF1)") (class "Default")
      (node (ref "R123") (pin "2") (pinfunction "2_2") (pintype "passive"))
      (node (ref "R133") (pin "2") (pinfunction "2_2") (pintype "passive"))
      (node (ref "R139") (pin "2") (pinfunction "2_2") (pintype "passive"))
      (node (ref "U5") (pin "9") (pinfunction "PA4-BEMF1_9") (pintype "passive"))
    )
    (net (code "175") (name "Net-(U5-PA8-TIM1_CH1)") (class "Default")
      (node (ref "U5") (pin "18") (pinfunction "PA8-TIM1_CH1_18") (pintype "passive"))
      (node (ref "U6") (pin "22") (pinfunction "HIN1_22") (pintype "passive"))
    )
    (net (code "176") (name "Net-(U5-PA9--TIM1_CH2)") (class "Default")
      (node (ref "U5") (pin "19") (pinfunction "PA9--TIM1_CH2_19") (pintype "passive"))
      (node (ref "U6") (pin "23") (pinfunction "HIN2_23") (pintype "passive"))
    )
    (net (code "177") (name "Net-(U5-PA10-TIM1_CH3)") (class "Default")
      (node (ref "U5") (pin "20") (pinfunction "PA10-TIM1_CH3_20") (pintype "passive"))
      (node (ref "U6") (pin "24") (pinfunction "HIN3_24") (pintype "passive"))
    )
    (net (code "178") (name "Net-(U5-PA11-TIM1_CH1N)") (class "Default")
      (node (ref "U5") (pin "21") (pinfunction "PA11-TIM1_CH1N_21") (pintype "passive"))
      (node (ref "U6") (pin "1") (pinfunction "LIN1_1") (pintype "passive"))
    )
    (net (code "179") (name "Net-(U5-PA12-TIM1_CH2N)") (class "Default")
      (node (ref "U5") (pin "22") (pinfunction "PA12-TIM1_CH2N_22") (pintype "passive"))
      (node (ref "U6") (pin "2") (pinfunction "LIN2_2") (pintype "passive"))
    )
    (net (code "180") (name "Net-(U5-PA13-LED_BLUE-SWDIO)") (class "Default")
      (node (ref "J18") (pin "1") (pinfunction "1_1") (pintype "passive"))
      (node (ref "U5") (pin "23") (pinfunction "PA13-LED_BLUE-SWDIO_23") (pintype "passive"))
    )
    (net (code "181") (name "Net-(U5-PA14-LED_GREE-SWCLK)") (class "Default")
      (node (ref "J20") (pin "1") (pinfunction "1_1") (pintype "passive"))
      (node (ref "U5") (pin "24") (pinfunction "PA14-LED_GREE-SWCLK_24") (pintype "passive"))
    )
    (net (code "182") (name "Net-(U5-PA15-SPI1_NSS)") (class "Default")
      (node (ref "R108") (pin "1") (pinfunction "1_1") (pintype "passive"))
      (node (ref "U5") (pin "25") (pinfunction "PA15-SPI1_NSS_25") (pintype "passive"))
    )
    (net (code "183") (name "Net-(U5-PB0--BEMF2)") (class "Default")
      (node (ref "R127") (pin "2") (pinfunction "2_2") (pintype "passive"))
      (node (ref "R134") (pin "2") (pinfunction "2_2") (pintype "passive"))
      (node (ref "R140") (pin "2") (pinfunction "2_2") (pintype "passive"))
      (node (ref "U5") (pin "13") (pinfunction "PB0--BEMF2_13") (pintype "passive"))
    )
    (net (code "184") (name "Net-(U5-PB3-SPI1_SCK)") (class "Default")
      (node (ref "R153") (pin "1") (pinfunction "1_1") (pintype "passive"))
      (node (ref "U5") (pin "26") (pinfunction "PB3-SPI1_SCK_26") (pintype "passive"))
    )
    (net (code "185") (name "Net-(U5-PB4-SPI1_MISO)") (class "Default")
      (node (ref "R149") (pin "1") (pinfunction "1_1") (pintype "passive"))
      (node (ref "U5") (pin "27") (pinfunction "PB4-SPI1_MISO_27") (pintype "passive"))
    )
    (net (code "186") (name "Net-(U5-PB5-SPI1_MOSI)") (class "Default")
      (node (ref "R151") (pin "1") (pinfunction "1_1") (pintype "passive"))
      (node (ref "U5") (pin "28") (pinfunction "PB5-SPI1_MOSI_28") (pintype "passive"))
    )
    (net (code "187") (name "Net-(U5-PF0-TIM1_CH3N)") (class "Default")
      (node (ref "U5") (pin "2") (pinfunction "PF0-TIM1_CH3N_2") (pintype "passive"))
      (node (ref "U6") (pin "3") (pinfunction "LIN3_3") (pintype "passive"))
    )
    (net (code "188") (name "Net-(U5-PF1--BEMF3)") (class "Default")
      (node (ref "R129") (pin "2") (pinfunction "2_2") (pintype "passive"))
      (node (ref "R135") (pin "2") (pinfunction "2_2") (pintype "passive"))
      (node (ref "R141") (pin "2") (pinfunction "2_2") (pintype "passive"))
      (node (ref "U5") (pin "3") (pinfunction "PF1--BEMF3_3") (pintype "passive"))
    )
    (net (code "189") (name "Net-(U6-HO1)") (class "Default")
      (node (ref "R73") (pin "1") (pinfunction "1_1") (pintype "passive"))
      (node (ref "U6") (pin "19") (pinfunction "HO1_19") (pintype "passive"))
    )
    (net (code "190") (name "Net-(U6-HO2)") (class "Default")
      (node (ref "R93") (pin "1") (pinfunction "1_1") (pintype "passive"))
      (node (ref "U6") (pin "16") (pinfunction "HO2_16") (pintype "passive"))
    )
    (net (code "191") (name "Net-(U6-HO3)") (class "Default")
      (node (ref "R114") (pin "1") (pinfunction "1_1") (pintype "passive"))
      (node (ref "U6") (pin "13") (pinfunction "HO3_13") (pintype "passive"))
    )
    (net (code "192") (name "Net-(U6-LO1)") (class "Default")
      (node (ref "R78") (pin "1") (pinfunction "1_1") (pintype "passive"))
      (node (ref "U6") (pin "11") (pinfunction "LO1_11") (pintype "passive"))
    )
    (net (code "193") (name "Net-(U6-LO2)") (class "Default")
      (node (ref "R95") (pin "1") (pinfunction "1_1") (pintype "passive"))
      (node (ref "U6") (pin "10") (pinfunction "LO2_10") (pintype "passive"))
    )
    (net (code "194") (name "Net-(U6-LO3)") (class "Default")
      (node (ref "R116") (pin "1") (pinfunction "1_1") (pintype "passive"))
      (node (ref "U6") (pin "9") (pinfunction "LO3_9") (pintype "passive"))
    )
    (net (code "195") (name "Net-(U6-VB1)") (class "Default")
      (node (ref "C49") (pin "2") (pinfunction "2_2") (pintype "passive"))
      (node (ref "D13") (pin "1") (pinfunction "1_1") (pintype "passive"))
      (node (ref "U6") (pin "20") (pinfunction "VB1_20") (pintype "passive"))
    )
    (net (code "196") (name "Net-(U6-VB2)") (class "Default")
      (node (ref "C54") (pin "2") (pinfunction "2_2") (pintype "passive"))
      (node (ref "D16") (pin "1") (pinfunction "1_1") (pintype "passive"))
      (node (ref "U6") (pin "17") (pinfunction "VB2_17") (pintype "passive"))
    )
    (net (code "197") (name "Net-(U6-VB3)") (class "Default")
      (node (ref "C59") (pin "2") (pinfunction "2_2") (pintype "passive"))
      (node (ref "D19") (pin "1") (pinfunction "1_1") (pintype "passive"))
      (node (ref "U6") (pin "14") (pinfunction "VB3_14") (pintype "passive"))
    )
    (net (code "198") (name "Net-(U7-BOOT0{slash}PB8)") (class "Default")
      (node (ref "R122") (pin "1") (pinfunction "1_1") (pintype "passive"))
      (node (ref "U7") (pin "31") (pinfunction "BOOT0/PB8_31") (pintype "passive"))
    )
    (net (code "199") (name "Net-(U7-NRST)") (class "Default")
      (node (ref "R113") (pin "2") (pinfunction "2_2") (pintype "passive"))
      (node (ref "U7") (pin "4") (pinfunction "NRST_4") (pintype "passive"))
    )
    (net (code "200") (name "Net-(U7-PA0-V-BUS)") (class "Default")
      (node (ref "R107") (pin "1") (pinfunction "1_1") (pintype "passive"))
      (node (ref "R111") (pin "2") (pinfunction "2_2") (pintype "passive"))
      (node (ref "U7") (pin "5") (pinfunction "PA0-V-BUS_5") (pintype "passive"))
    )
    (net (code "201") (name "Net-(U7-PA4-BEMF1)") (class "Default")
      (node (ref "R120") (pin "2") (pinfunction "2_2") (pintype "passive"))
      (node (ref "R130") (pin "2") (pinfunction "2_2") (pintype "passive"))
      (node (ref "R136") (pin "2") (pinfunction "2_2") (pintype "passive"))
      (node (ref "U7") (pin "9") (pinfunction "PA4-BEMF1_9") (pintype "passive"))
    )
    (net (code "202") (name "Net-(U7-PA8-TIM1_CH1)") (class "Default")
      (node (ref "U7") (pin "18") (pinfunction "PA8-TIM1_CH1_18") (pintype "passive"))
      (node (ref "U8") (pin "22") (pinfunction "HIN1_22") (pintype "passive"))
    )
    (net (code "203") (name "Net-(U7-PA9--TIM1_CH2)") (class "Default")
      (node (ref "U7") (pin "19") (pinfunction "PA9--TIM1_CH2_19") (pintype "passive"))
      (node (ref "U8") (pin "23") (pinfunction "HIN2_23") (pintype "passive"))
    )
    (net (code "204") (name "Net-(U7-PA10-TIM1_CH3)") (class "Default")
      (node (ref "U7") (pin "20") (pinfunction "PA10-TIM1_CH3_20") (pintype "passive"))
      (node (ref "U8") (pin "24") (pinfunction "HIN3_24") (pintype "passive"))
    )
    (net (code "205") (name "Net-(U7-PA11-TIM1_CH1N)") (class "Default")
      (node (ref "U7") (pin "21") (pinfunction "PA11-TIM1_CH1N_21") (pintype "passive"))
      (node (ref "U8") (pin "1") (pinfunction "LIN1_1") (pintype "passive"))
    )
    (net (code "206") (name "Net-(U7-PA12-TIM1_CH2N)") (class "Default")
      (node (ref "U7") (pin "22") (pinfunction "PA12-TIM1_CH2N_22") (pintype "passive"))
      (node (ref "U8") (pin "2") (pinfunction "LIN2_2") (pintype "passive"))
    )
    (net (code "207") (name "Net-(U7-PA13-LED_BLUE-SWDIO)") (class "Default")
      (node (ref "J19") (pin "1") (pinfunction "1_1") (pintype "passive"))
      (node (ref "U7") (pin "23") (pinfunction "PA13-LED_BLUE-SWDIO_23") (pintype "passive"))
    )
    (net (code "208") (name "Net-(U7-PA14-LED_GREE-SWCLK)") (class "Default")
      (node (ref "J21") (pin "1") (pinfunction "1_1") (pintype "passive"))
      (node (ref "U7") (pin "24") (pinfunction "PA14-LED_GREE-SWCLK_24") (pintype "passive"))
    )
    (net (code "209") (name "Net-(U7-PA15-SPI1_NSS)") (class "Default")
      (node (ref "R109") (pin "1") (pinfunction "1_1") (pintype "passive"))
      (node (ref "U7") (pin "25") (pinfunction "PA15-SPI1_NSS_25") (pintype "passive"))
    )
    (net (code "210") (name "Net-(U7-PB0--BEMF2)") (class "Default")
      (node (ref "R126") (pin "2") (pinfunction "2_2") (pintype "passive"))
      (node (ref "R131") (pin "2") (pinfunction "2_2") (pintype "passive"))
      (node (ref "R137") (pin "2") (pinfunction "2_2") (pintype "passive"))
      (node (ref "U7") (pin "13") (pinfunction "PB0--BEMF2_13") (pintype "passive"))
    )
    (net (code "211") (name "Net-(U7-PB3-SPI1_SCK)") (class "Default")
      (node (ref "R154") (pin "1") (pinfunction "1_1") (pintype "passive"))
      (node (ref "U7") (pin "26") (pinfunction "PB3-SPI1_SCK_26") (pintype "passive"))
    )
    (net (code "212") (name "Net-(U7-PB4-SPI1_MISO)") (class "Default")
      (node (ref "R150") (pin "1") (pinfunction "1_1") (pintype "passive"))
      (node (ref "U7") (pin "27") (pinfunction "PB4-SPI1_MISO_27") (pintype "passive"))
    )
    (net (code "213") (name "Net-(U7-PB5-SPI1_MOSI)") (class "Default")
      (node (ref "R152") (pin "1") (pinfunction "1_1") (pintype "passive"))
      (node (ref "U7") (pin "28") (pinfunction "PB5-SPI1_MOSI_28") (pintype "passive"))
    )
    (net (code "214") (name "Net-(U7-PF0-TIM1_CH3N)") (class "Default")
      (node (ref "U7") (pin "2") (pinfunction "PF0-TIM1_CH3N_2") (pintype "passive"))
      (node (ref "U8") (pin "3") (pinfunction "LIN3_3") (pintype "passive"))
    )
    (net (code "215") (name "Net-(U7-PF1--BEMF3)") (class "Default")
      (node (ref "R128") (pin "2") (pinfunction "2_2") (pintype "passive"))
      (node (ref "R132") (pin "2") (pinfunction "2_2") (pintype "passive"))
      (node (ref "R138") (pin "2") (pinfunction "2_2") (pintype "passive"))
      (node (ref "U7") (pin "3") (pinfunction "PF1--BEMF3_3") (pintype "passive"))
    )
    (net (code "216") (name "Net-(U8-HO1)") (class "Default")
      (node (ref "R74") (pin "1") (pinfunction "1_1") (pintype "passive"))
      (node (ref "U8") (pin "19") (pinfunction "HO1_19") (pintype "passive"))
    )
    (net (code "217") (name "Net-(U8-HO2)") (class "Default")
      (node (ref "R94") (pin "1") (pinfunction "1_1") (pintype "passive"))
      (node (ref "U8") (pin "16") (pinfunction "HO2_16") (pintype "passive"))
    )
    (net (code "218") (name "Net-(U8-HO3)") (class "Default")
      (node (ref "R115") (pin "1") (pinfunction "1_1") (pintype "passive"))
      (node (ref "U8") (pin "13") (pinfunction "HO3_13") (pintype "passive"))
    )
    (net (code "219") (name "Net-(U8-LO1)") (class "Default")
      (node (ref "R80") (pin "1") (pinfunction "1_1") (pintype "passive"))
      (node (ref "U8") (pin "11") (pinfunction "LO1_11") (pintype "passive"))
    )
    (net (code "220") (name "Net-(U8-LO2)") (class "Default")
      (node (ref "R96") (pin "1") (pinfunction "1_1") (pintype "passive"))
      (node (ref "U8") (pin "10") (pinfunction "LO2_10") (pintype "passive"))
    )
    (net (code "221") (name "Net-(U8-LO3)") (class "Default")
      (node (ref "R117") (pin "1") (pinfunction "1_1") (pintype "passive"))
      (node (ref "U8") (pin "9") (pinfunction "LO3_9") (pintype "passive"))
    )
    (net (code "222") (name "Net-(U8-VB1)") (class "Default")
      (node (ref "C50") (pin "2") (pinfunction "2_2") (pintype "passive"))
      (node (ref "D14") (pin "1") (pinfunction "1_1") (pintype "passive"))
      (node (ref "U8") (pin "20") (pinfunction "VB1_20") (pintype "passive"))
    )
    (net (code "223") (name "Net-(U8-VB2)") (class "Default")
      (node (ref "C55") (pin "2") (pinfunction "2_2") (pintype "passive"))
      (node (ref "D17") (pin "1") (pinfunction "1_1") (pintype "passive"))
      (node (ref "U8") (pin "17") (pinfunction "VB2_17") (pintype "passive"))
    )
    (net (code "224") (name "Net-(U8-VB3)") (class "Default")
      (node (ref "C60") (pin "2") (pinfunction "2_2") (pintype "passive"))
      (node (ref "D20") (pin "1") (pinfunction "1_1") (pintype "passive"))
      (node (ref "U8") (pin "14") (pinfunction "VB3_14") (pintype "passive"))
    )
    (net (code "225") (name "Net-(U9-BST)") (class "Default")
      (node (ref "C51") (pin "2") (pinfunction "2_2") (pintype "passive"))
      (node (ref "U9") (pin "10") (pinfunction "BST_10") (pintype "passive"))
    )
    (net (code "226") (name "Net-(U9-COMP)") (class "Default")
      (node (ref "C58") (pin "2") (pinfunction "2_2") (pintype "passive"))
      (node (ref "U9") (pin "4") (pinfunction "COMP_4") (pintype "passive"))
    )
    (net (code "227") (name "Net-(U9-EN)") (class "Default")
      (node (ref "R91") (pin "2") (pinfunction "2_2") (pintype "passive"))
      (node (ref "U9") (pin "3") (pinfunction "EN_3") (pintype "passive"))
    )
    (net (code "228") (name "Net-(U9-FB)") (class "Default")
      (node (ref "R102") (pin "1") (pinfunction "1_1") (pintype "passive"))
      (node (ref "R92") (pin "2") (pinfunction "2_2") (pintype "passive"))
      (node (ref "U9") (pin "5") (pinfunction "FB_5") (pintype "passive"))
    )
    (net (code "229") (name "Net-(U9-FREQ)") (class "Default")
      (node (ref "R99") (pin "1") (pinfunction "1_1") (pintype "passive"))
      (node (ref "U9") (pin "7") (pinfunction "FREQ_7") (pintype "passive"))
    )
    (net (code "230") (name "Net-(U11-BYP)") (class "Default")
      (node (ref "C82") (pin "2") (pinfunction "2_2") (pintype "passive"))
      (node (ref "U11") (pin "4") (pinfunction "BYP_4") (pintype "passive"))
    )
    (net (code "231") (name "Net-(U12-BYP)") (class "Default")
      (node (ref "C22") (pin "2") (pinfunction "2_2") (pintype "passive"))
      (node (ref "U12") (pin "4") (pinfunction "BYP_4") (pintype "passive"))
    )
    (net (code "232") (name "Net-(U13-BYP)") (class "Default")
      (node (ref "C27") (pin "2") (pinfunction "2_2") (pintype "passive"))
      (node (ref "U13") (pin "4") (pinfunction "BYP_4") (pintype "passive"))
    )
    (net (code "233") (name "VBAT") (class "Default")
      (node (ref "C1") (pin "1") (pinfunction "1_1") (pintype "passive"))
      (node (ref "C10") (pin "1") (pinfunction "1_1") (pintype "passive"))
      (node (ref "C2") (pin "1") (pinfunction "1_1") (pintype "passive"))
      (node (ref "C3") (pin "1") (pinfunction "1_1") (pintype "passive"))
      (node (ref "C37") (pin "1") (pinfunction "1_1") (pintype "passive"))
      (node (ref "C38") (pin "1") (pinfunction "1_1") (pintype "passive"))
      (node (ref "C39") (pin "1") (pinfunction "1_1") (pintype "passive"))
      (node (ref "C4") (pin "1") (pinfunction "1_1") (pintype "passive"))
      (node (ref "C40") (pin "1") (pinfunction "1_1") (pintype "passive"))
      (node (ref "C41") (pin "1") (pinfunction "1_1") (pintype "passive"))
      (node (ref "C42") (pin "1") (pinfunction "1_1") (pintype "passive"))
      (node (ref "C43") (pin "1") (pinfunction "1_1") (pintype "passive"))
      (node (ref "C44") (pin "1") (pinfunction "1_1") (pintype "passive"))
      (node (ref "C45") (pin "1") (pinfunction "1_1") (pintype "passive"))
      (node (ref "C46") (pin "1") (pinfunction "1_1") (pintype "passive"))
      (node (ref "C5") (pin "1") (pinfunction "1_1") (pintype "passive"))
      (node (ref "C6") (pin "1") (pinfunction "1_1") (pintype "passive"))
      (node (ref "C7") (pin "1") (pinfunction "1_1") (pintype "passive"))
      (node (ref "C8") (pin "1") (pinfunction "1_1") (pintype "passive"))
      (node (ref "C9") (pin "1") (pinfunction "1_1") (pintype "passive"))
      (node (ref "D15") (pin "2") (pinfunction "CATHODE_2") (pintype "passive"))
      (node (ref "J17") (pin "2") (pinfunction "2_2") (pintype "passive"))
      (node (ref "J24") (pin "1") (pinfunction "1_1") (pintype "passive"))
      (node (ref "Q1") (pin "5") (pinfunction "D_5") (pintype "passive"))
      (node (ref "Q10") (pin "5") (pinfunction "D_5") (pintype "passive"))
      (node (ref "Q13") (pin "5") (pinfunction "D_5") (pintype "passive"))
      (node (ref "Q14") (pin "5") (pinfunction "D_5") (pintype "passive"))
      (node (ref "Q17") (pin "5") (pinfunction "D_5") (pintype "passive"))
      (node (ref "Q18") (pin "5") (pinfunction "D_5") (pintype "passive"))
      (node (ref "Q2") (pin "5") (pinfunction "D_5") (pintype "passive"))
      (node (ref "Q21") (pin "5") (pinfunction "D_5") (pintype "passive"))
      (node (ref "Q22") (pin "5") (pinfunction "D_5") (pintype "passive"))
      (node (ref "Q5") (pin "5") (pinfunction "D_5") (pintype "passive"))
      (node (ref "Q6") (pin "5") (pinfunction "D_5") (pintype "passive"))
      (node (ref "Q9") (pin "5") (pinfunction "D_5") (pintype "passive"))
      (node (ref "R106") (pin "2") (pinfunction "2_2") (pintype "passive"))
      (node (ref "R107") (pin "2") (pinfunction "2_2") (pintype "passive"))
      (node (ref "R33") (pin "2") (pinfunction "2_2") (pintype "passive"))
      (node (ref "R34") (pin "2") (pinfunction "2_2") (pintype "passive"))
    )
    (net (code "234") (name "unconnected-(1-Pad1)") (class "Default")
      (node (ref "1") (pin "1") (pinfunction "1_1") (pintype "passive"))
    )
    (net (code "235") (name "unconnected-(2-Pad1)") (class "Default")
      (node (ref "2") (pin "1") (pinfunction "1_1") (pintype "passive"))
    )
    (net (code "236") (name "unconnected-(3-Pad1)") (class "Default")
      (node (ref "3") (pin "1") (pinfunction "1_1") (pintype "passive"))
    )
    (net (code "237") (name "unconnected-(4-Pad1)") (class "Default")
      (node (ref "4") (pin "1") (pinfunction "1_1") (pintype "passive"))
    )
    (net (code "238") (name "unconnected-(LED3-DO-Pad3)") (class "Default")
      (node (ref "LED3") (pin "3") (pinfunction "DO_3") (pintype "passive"))
    )
    (net (code "239") (name "unconnected-(LED4-DO-Pad3)") (class "Default")
      (node (ref "LED4") (pin "3") (pinfunction "DO_3") (pintype "passive"))
    )
    (net (code "240") (name "unconnected-(LED5-DO-Pad3)") (class "Default")
      (node (ref "LED5") (pin "3") (pinfunction "DO_3") (pintype "passive"))
    )
    (net (code "241") (name "unconnected-(LED6-DO-Pad3)") (class "Default")
      (node (ref "LED6") (pin "3") (pinfunction "DO_3") (pintype "passive"))
    )
    (net (code "242") (name "unconnected-(U1-PA2-Pad7)") (class "Default")
      (node (ref "U1") (pin "7") (pinfunction "PA2_7") (pintype "passive"))
    )
    (net (code "243") (name "unconnected-(U1-PA6-Pad11)") (class "Default")
      (node (ref "U1") (pin "11") (pinfunction "PA6_11") (pintype "passive"))
    )
    (net (code "244") (name "unconnected-(U3-PA2-Pad7)") (class "Default")
      (node (ref "U3") (pin "7") (pinfunction "PA2_7") (pintype "passive"))
    )
    (net (code "245") (name "unconnected-(U3-PA6-Pad11)") (class "Default")
      (node (ref "U3") (pin "11") (pinfunction "PA6_11") (pintype "passive"))
    )
    (net (code "246") (name "unconnected-(U5-PA2-Pad7)") (class "Default")
      (node (ref "U5") (pin "7") (pinfunction "PA2_7") (pintype "passive"))
    )
    (net (code "247") (name "unconnected-(U5-PA6-Pad11)") (class "Default")
      (node (ref "U5") (pin "11") (pinfunction "PA6_11") (pintype "passive"))
    )
    (net (code "248") (name "unconnected-(U7-PA2-Pad7)") (class "Default")
      (node (ref "U7") (pin "7") (pinfunction "PA2_7") (pintype "passive"))
    )
    (net (code "249") (name "unconnected-(U7-PA6-Pad11)") (class "Default")
      (node (ref "U7") (pin "11") (pinfunction "PA6_11") (pintype "passive"))
    )
  )
)
